# permamote.net
KiCad netlist of a schematic drawn in EAGLE
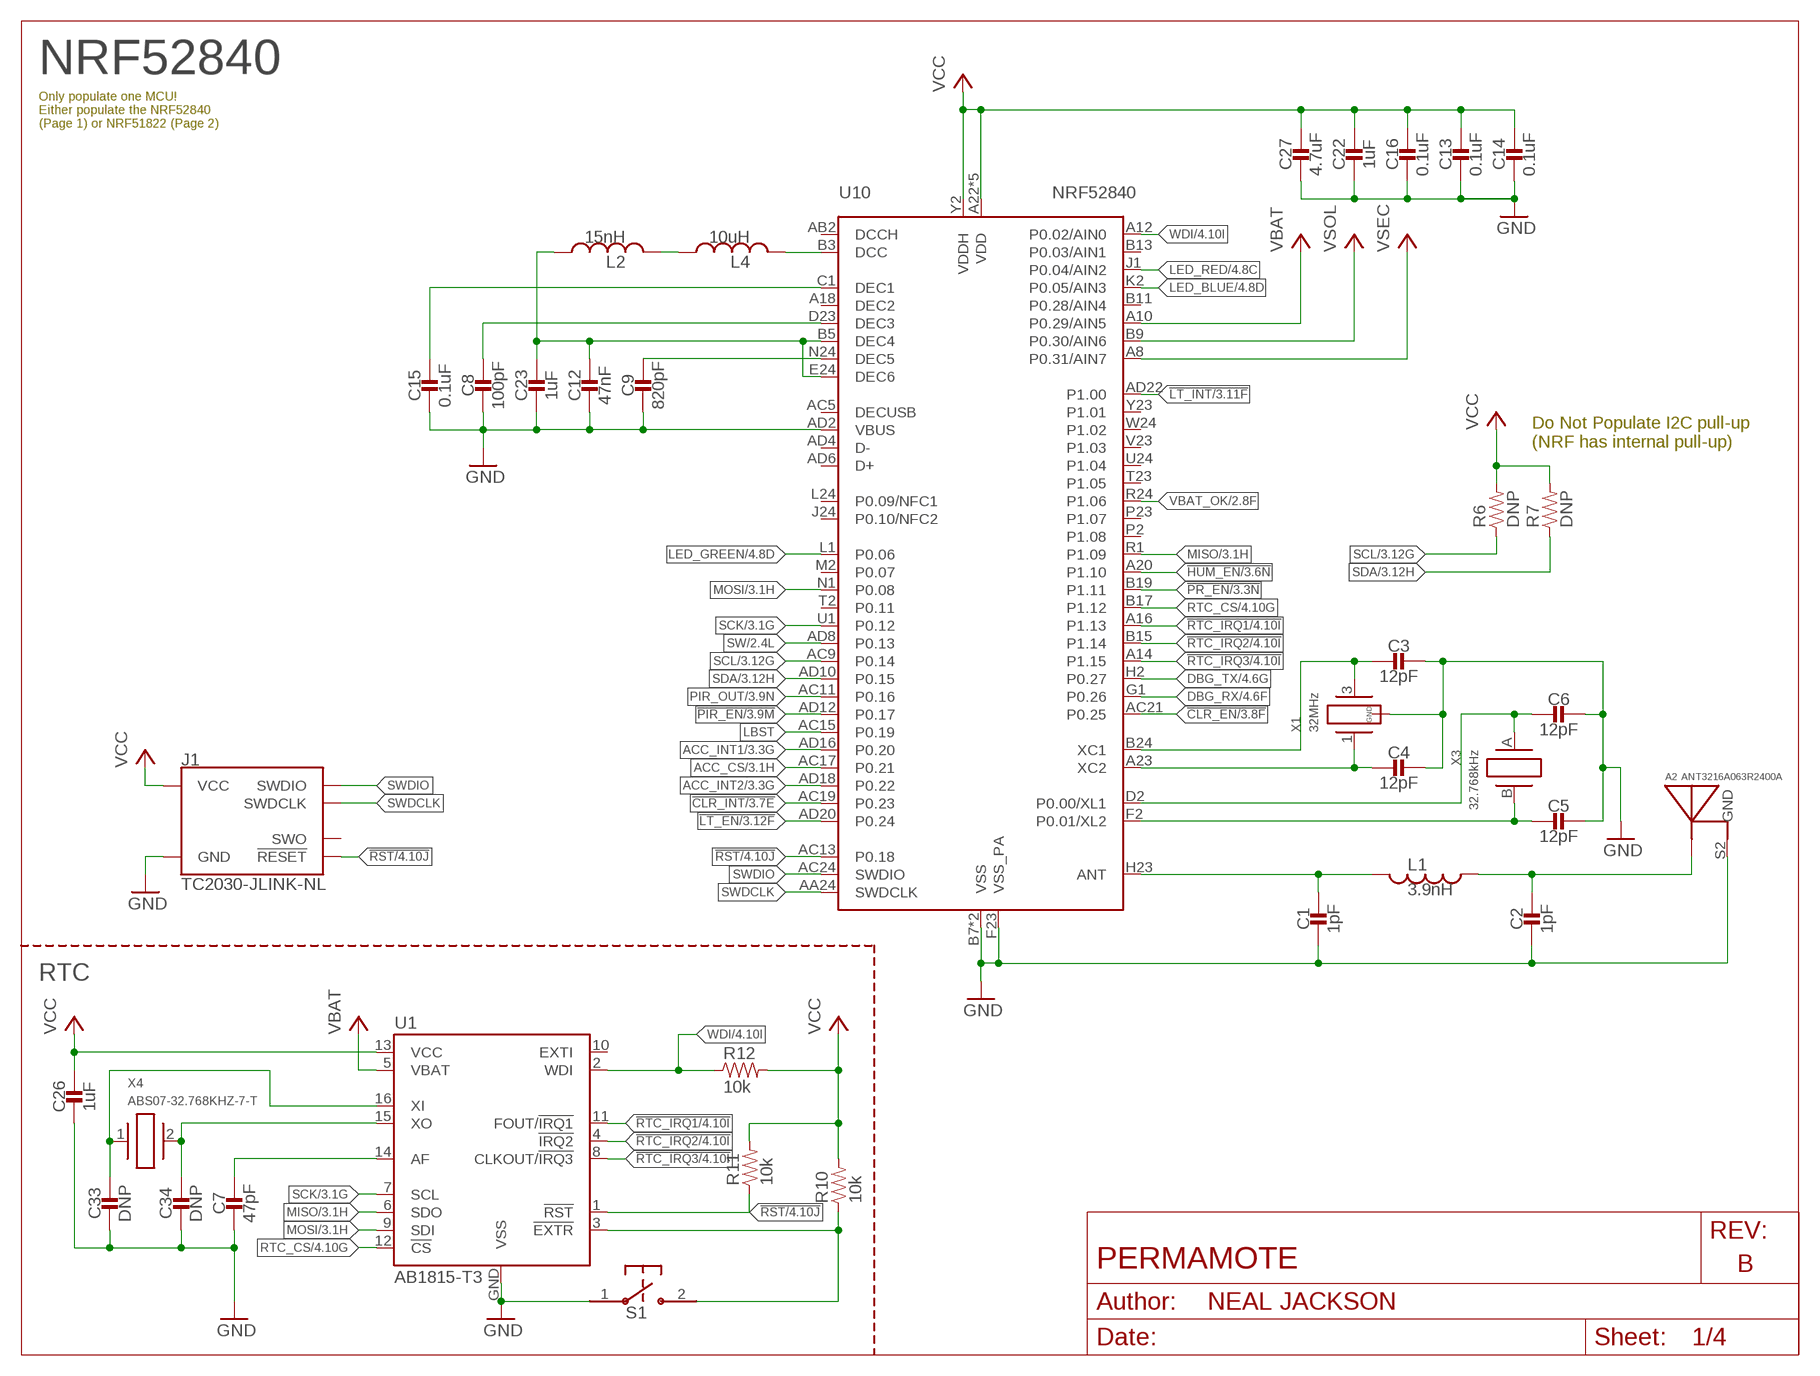
[diagram p0: schematic, sheet 1]
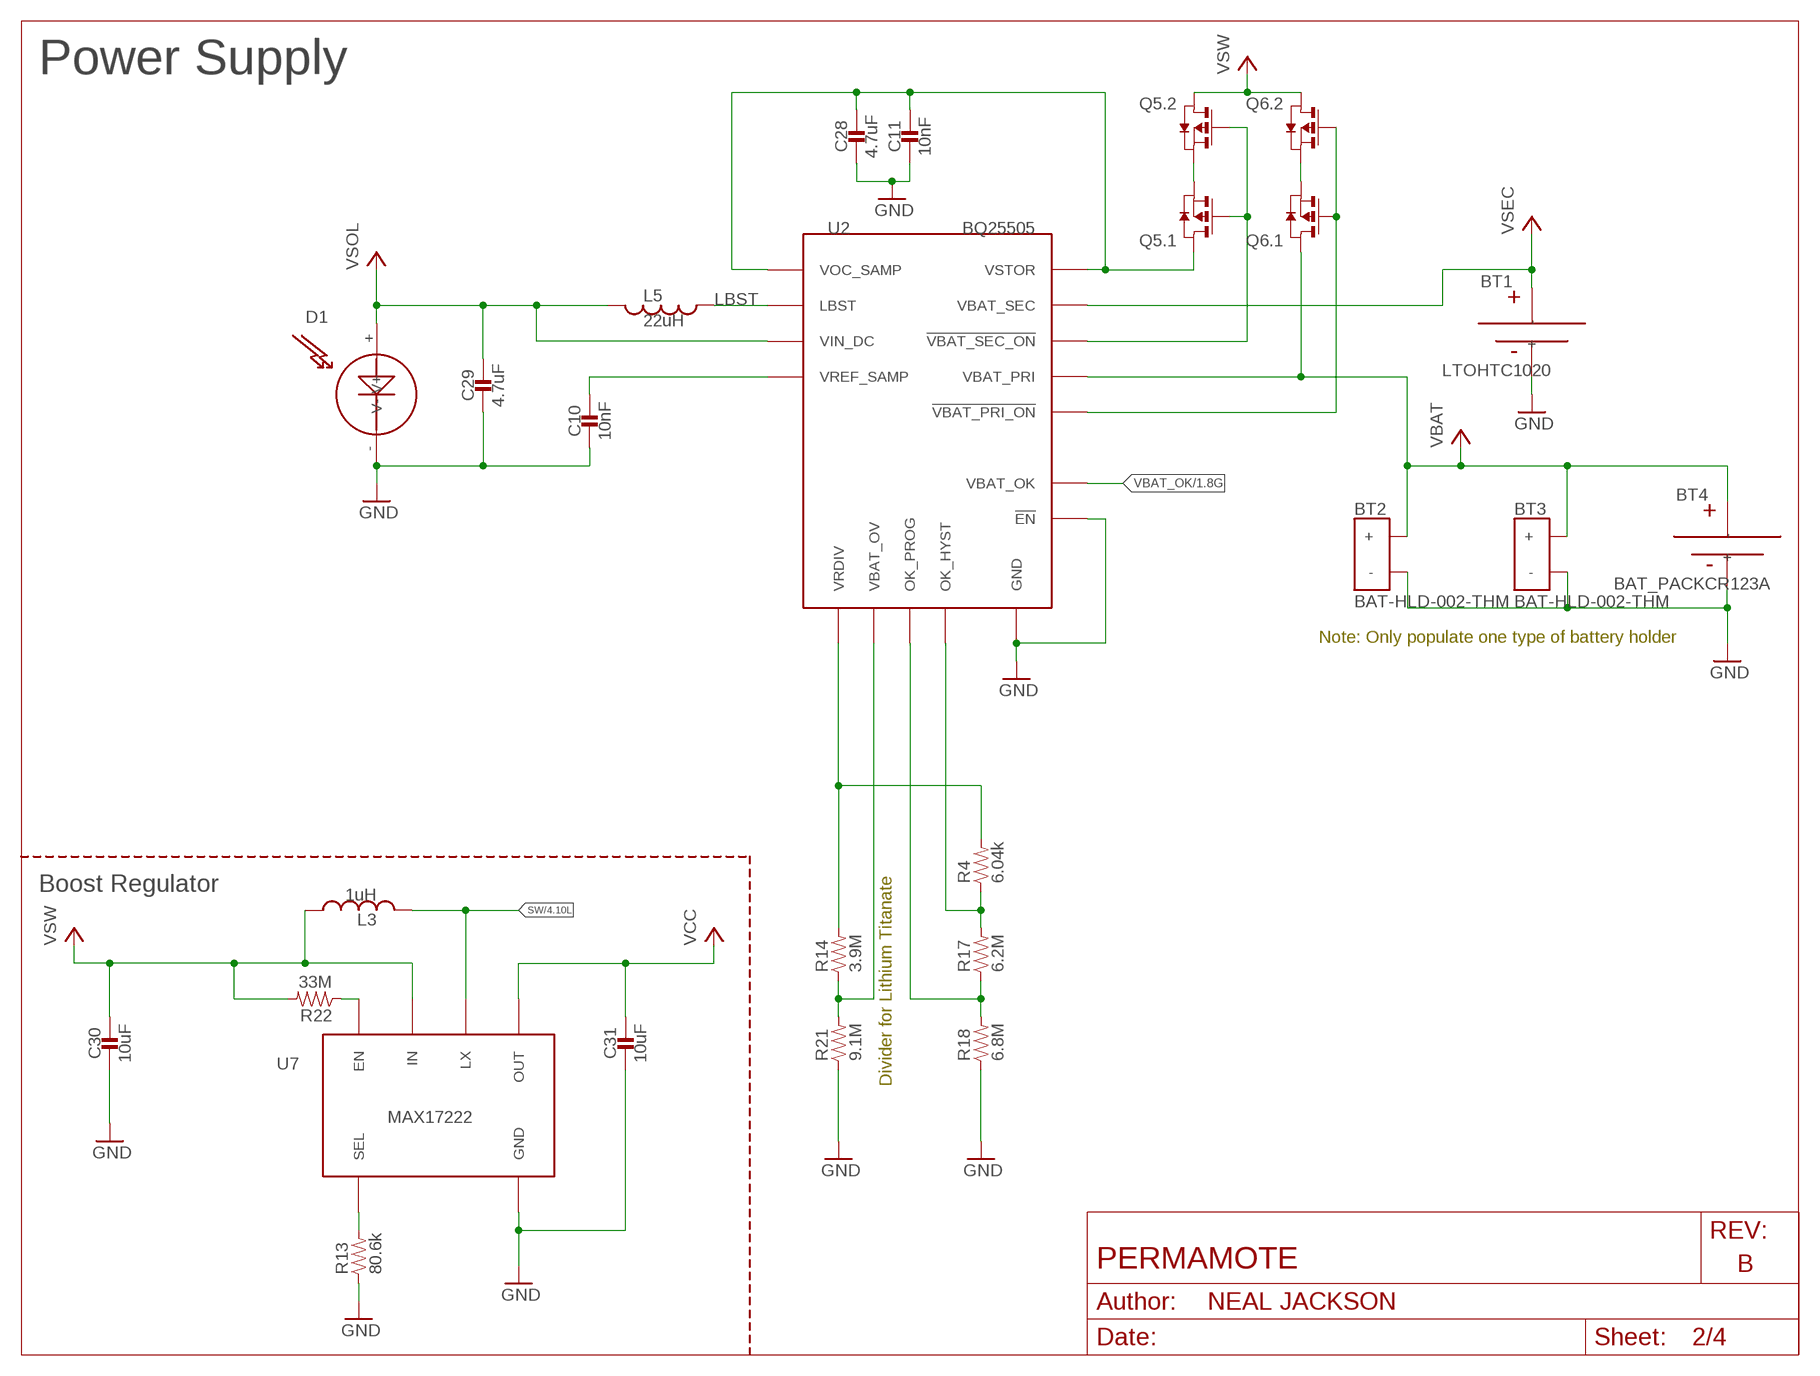
[diagram p1: schematic, sheet 2]
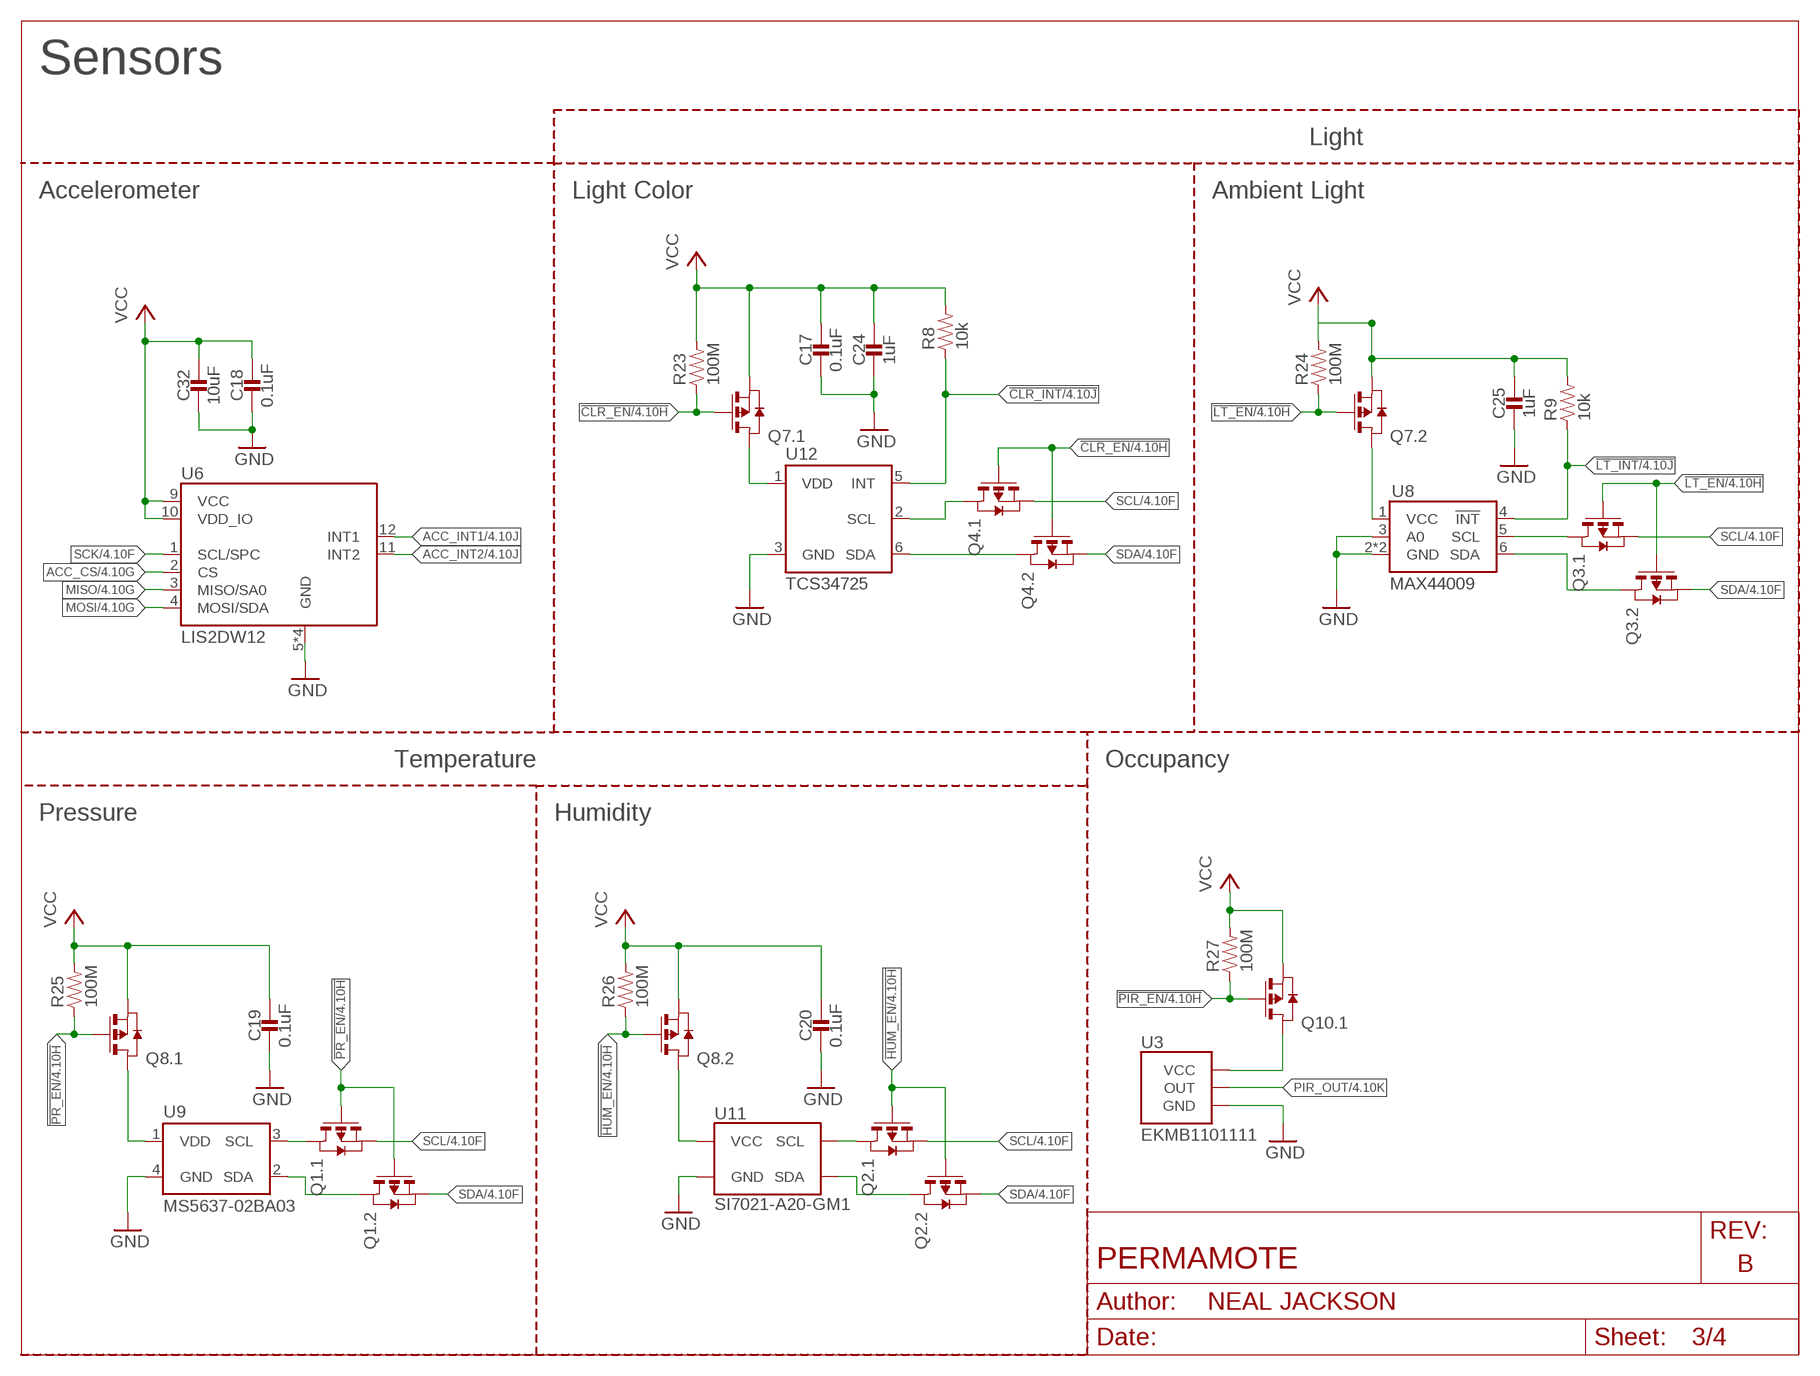
[diagram p2: schematic, sheet 3]
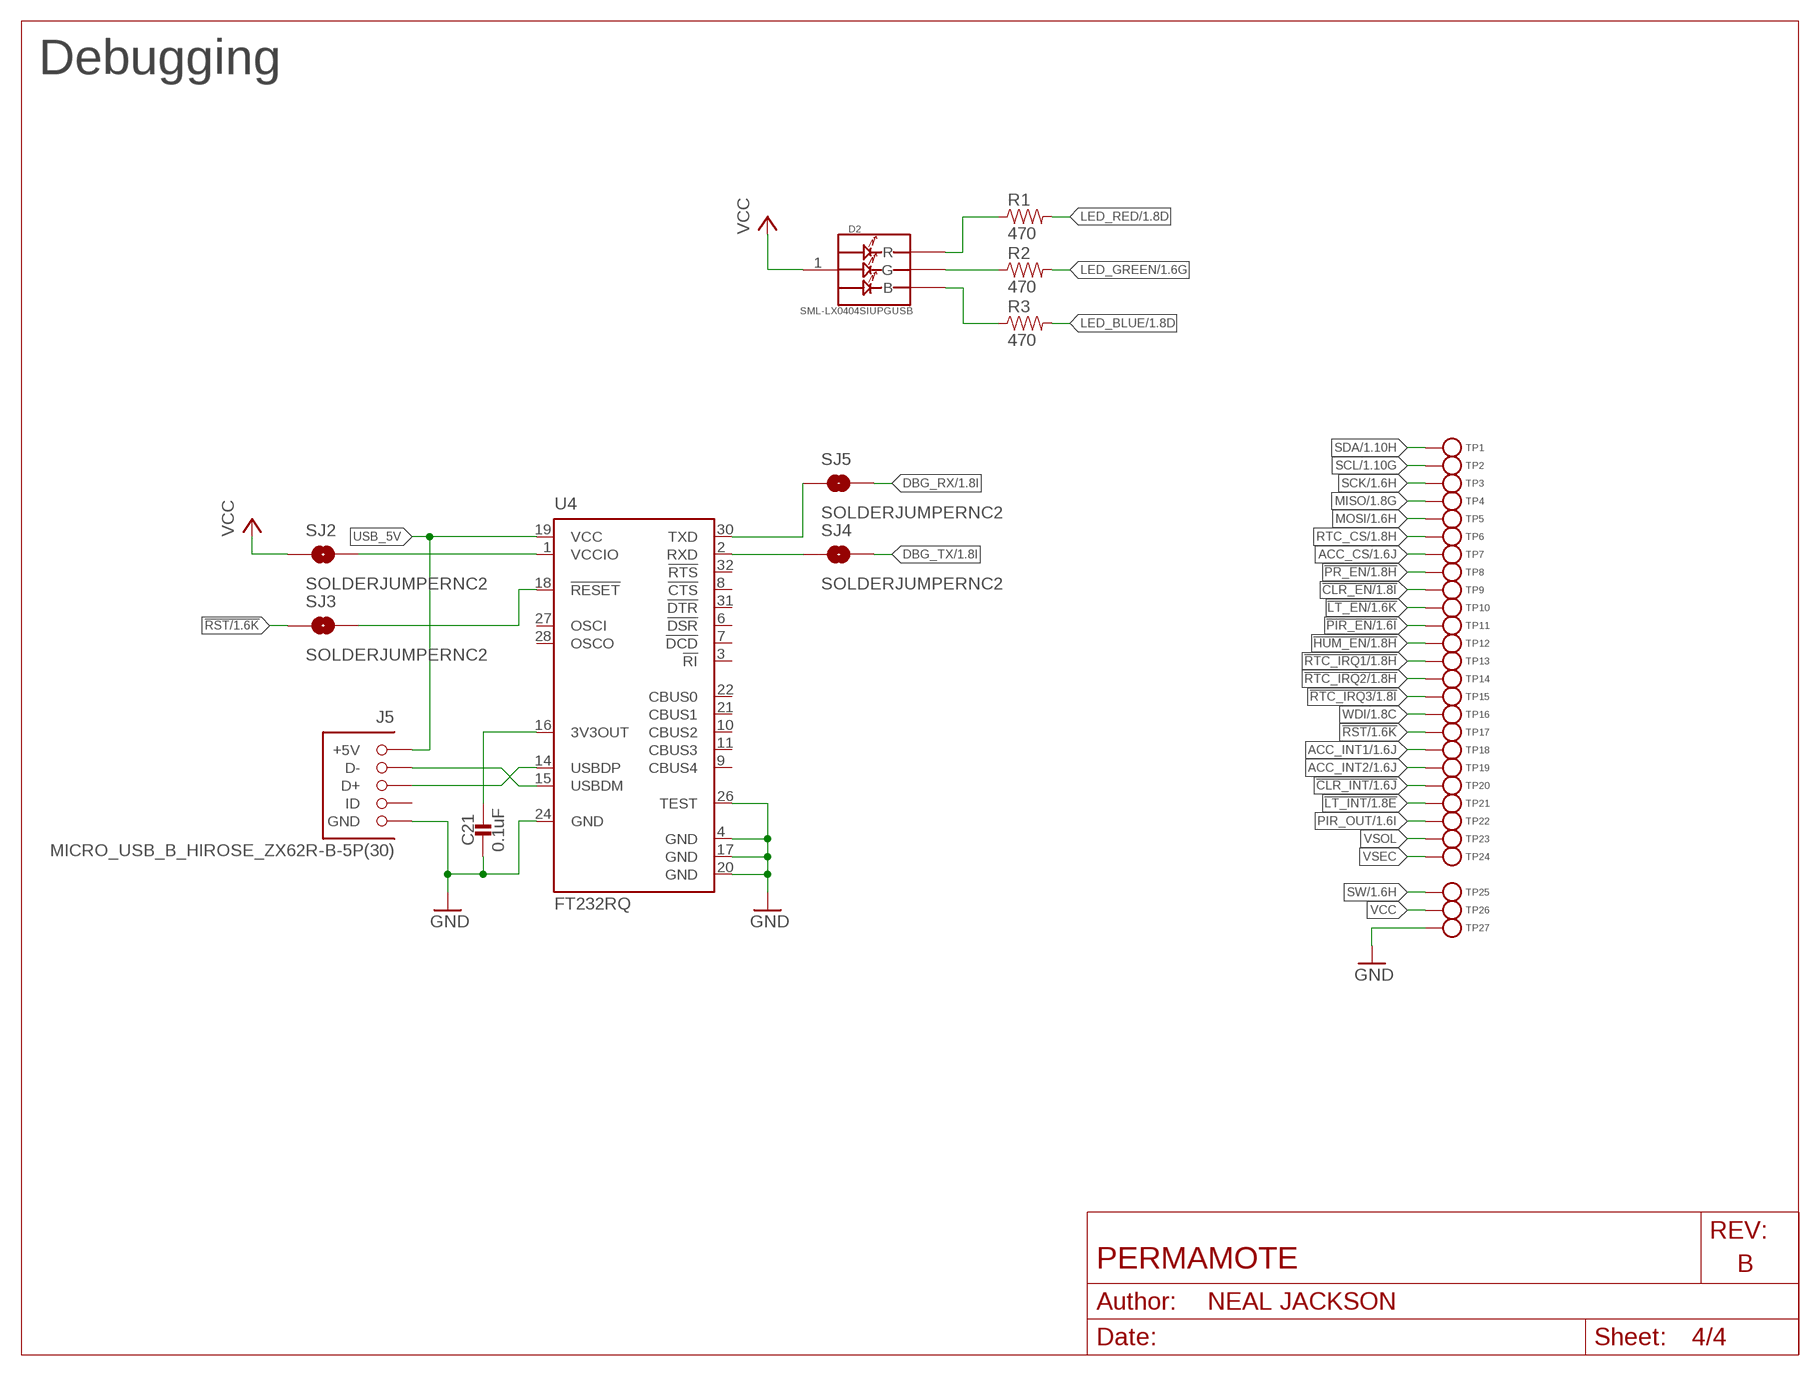
[diagram p3: schematic, sheet 4]

(export (version "E")
  (design (tool "Eeschema 10.0.6"))
  (components
    (comp (ref "BT1")
      (value "LTOHTC1020")
      (footprint "eagle-import:1020")
      (libsource (lib "eagle-import") (part "LTOHTC1020"))
    )
    (comp (ref "BT2")
      (value "BAT-HLD-002-THM")
      (footprint "eagle-import:BAT-HLD-002-THM")
      (fields
        (field (name "DIGIKEY") "BAT-HLD-001-THM-ND")
        (field (name "MOUSER") "712-BAT-HLD-001-THM")
        (field (name "MPN") "BAT-HLD-001-THM")
      )
      (libsource (lib "eagle-import") (part "BAT-HLD-002-THM"))
    )
    (comp (ref "BT3")
      (value "BAT-HLD-002-THM")
      (footprint "eagle-import:BAT-HLD-002-THM")
      (fields
        (field (name "DIGIKEY") "BAT-HLD-001-THM-ND")
        (field (name "MOUSER") "712-BAT-HLD-001-THM")
        (field (name "MPN") "BAT-HLD-001-THM")
      )
      (libsource (lib "eagle-import") (part "BAT-HLD-002-THM"))
    )
    (comp (ref "BT4")
      (value "BAT_PACKCR123A")
      (footprint "eagle-import:BH123A")
      (fields (field (name "MANUFACTURER") "MPD") (field (name "MPN") "BH123A"))
      (libsource (lib "eagle-import") (part "BAT_PACKCR123A"))
    )
    (comp (ref "C10")
      (value "10nF")
      (footprint "eagle-import:0402_CAP")
      (fields (field (name "MPN") "GRM155R71H103KA88D "))
      (libsource (lib "eagle-import") (part "CAPACITOR0402_CAP"))
    )
    (comp (ref "C11")
      (value "10nF")
      (footprint "eagle-import:0402_CAP")
      (fields (field (name "MPN") "GRM155R71H103KA88D "))
      (libsource (lib "eagle-import") (part "CAPACITOR0402_CAP"))
    )
    (comp (ref "C28")
      (value "4.7uF")
      (footprint "eagle-import:0402_CAP")
      (fields (field (name "MPN") "C1005X5R0J475K050BC "))
      (libsource (lib "eagle-import") (part "CAPACITOR0402_CAP"))
    )
    (comp (ref "C29")
      (value "4.7uF")
      (footprint "eagle-import:0402_CAP")
      (fields (field (name "MPN") "C1005X5R0J475K050BC "))
      (libsource (lib "eagle-import") (part "CAPACITOR0402_CAP"))
    )
    (comp (ref "C30")
      (value "10uF")
      (footprint "eagle-import:0603_CAP")
      (fields (field (name "MPN") "GRM188R60J106ME47D "))
      (libsource (lib "eagle-import") (part "CAPACITOR0603_CAP"))
    )
    (comp (ref "C31")
      (value "10uF")
      (footprint "eagle-import:0603_CAP")
      (fields (field (name "MPN") "GRM188R60J106ME47D "))
      (libsource (lib "eagle-import") (part "CAPACITOR0603_CAP"))
    )
    (comp (ref "D1")
      (value "SOLARCELLHOLES")
      (footprint "eagle-import:SOLAR_HOLES")
      (fields (field (name "MPN") "AM-1454CA"))
      (libsource (lib "eagle-import") (part "SOLARCELLHOLES"))
    )
    (comp (ref "L3")
      (value "1uH")
      (footprint "eagle-import:IHL-1212BZ-11")
      (fields
        (field (name "MANUFACTURER") "Vishay Dale")
        (field (name "MPN") "IHLP1212BZER2R2M11")
        (field (name "DIGIKEY") "541-1319-1-ND")
        (field (name "MPN_1") "IHLP1212BZER1R0M11")
      )
      (libsource (lib "eagle-import") (part "INDUCTORIHL"))
    )
    (comp (ref "L5")
      (value "22uH")
      (footprint "eagle-import:74437324220")
      (fields (field (name "DIGIKEY") "732-3340-1-ND") (field (name "MPN") "74437324220 "))
      (libsource (lib "eagle-import") (part "INDUCTOR74437324220"))
    )
    (comp (ref "Q5")
      (value "PMDXB950UPEL")
      (footprint "eagle-import:XDFN-6")
      (fields (field (name "MANUFACTURER") "NEXPERIA") (field (name "MPN") "PMDXB950UPELZ"))
      (libsource (lib "eagle-import") (part "PMDXB950UPEL"))
    )
    (comp (ref "Q6")
      (value "PMDXB950UPEL")
      (footprint "eagle-import:XDFN-6")
      (fields (field (name "MANUFACTURER") "NEXPERIA") (field (name "MPN") "PMDXB950UPELZ"))
      (libsource (lib "eagle-import") (part "PMDXB950UPEL"))
    )
    (comp (ref "R4")
      (value "6.04k")
      (footprint "eagle-import:0402_RES")
      (fields (field (name "MPN") "RC0402FR-076K04L"))
      (libsource (lib "eagle-import") (part "RESISTOR0402_RES"))
    )
    (comp (ref "R13")
      (value "80.6k")
      (footprint "eagle-import:0603-RES")
      (fields (field (name "MPN") "RC0603FR-0780K6L "))
      (libsource (lib "eagle-import") (part "RESISTOR0603_RES"))
    )
    (comp (ref "R14")
      (value "3.9M")
      (footprint "eagle-import:0402_RES")
      (fields (field (name "MPN") "RC0402JR-073M9L"))
      (libsource (lib "eagle-import") (part "RESISTOR0402_RES"))
    )
    (comp (ref "R17")
      (value "6.2M")
      (footprint "eagle-import:0402_RES")
      (fields (field (name "MPN") "RC0402JR-076M2L"))
      (libsource (lib "eagle-import") (part "RESISTOR0402_RES"))
    )
    (comp (ref "R18")
      (value "6.8M")
      (footprint "eagle-import:0402_RES")
      (fields (field (name "MPN") "RC0402JR-076M8L"))
      (libsource (lib "eagle-import") (part "RESISTOR0402_RES"))
    )
    (comp (ref "R21")
      (value "9.1M")
      (footprint "eagle-import:0402_RES")
      (fields (field (name "MPN") "RC0402JR-079M1L"))
      (libsource (lib "eagle-import") (part "RESISTOR0402_RES"))
    )
    (comp (ref "R22")
      (value "33M")
      (footprint "eagle-import:0603-RES")
      (fields (field (name "MPN") "HMC0603JT33M0 "))
      (libsource (lib "eagle-import") (part "RESISTOR0603_RES"))
    )
    (comp (ref "U2")
      (value "BQ25505")
      (footprint "eagle-import:S-PVQFN-N20-RGR")
      (fields (field (name "MANUFACTURER") "TI") (field (name "MPN") "BQ25505RGRR"))
      (libsource (lib "eagle-import") (part "BQ25505"))
    )
    (comp (ref "U7")
      (value "MAX17222")
      (footprint "eagle-import:UDFN-6-MAXIM")
      (fields (field (name "MANUFACTURER") "MAXIM INTEGRATED") (field (name "MPN") "MAX17222ELT+T"))
      (libsource (lib "eagle-import") (part "MAX17222"))
    )
    (comp (ref "A2")
      (value "ANT3216A063R2400A")
      (footprint "eagle-import:ANT3216A063R2400A")
      (fields (field (name "MANUFACTURER") "YAGEO"))
      (libsource (lib "eagle-import") (part "ANT3216A063R2400A"))
    )
    (comp (ref "C1")
      (value "1pF")
      (footprint "eagle-import:0402_CAP")
      (fields (field (name "MPN") "CL05C010CB5NNNC"))
      (libsource (lib "eagle-import") (part "CAPACITOR0402_CAP"))
    )
    (comp (ref "C2")
      (value "1pF")
      (footprint "eagle-import:0402_CAP")
      (fields (field (name "MPN") "CL05C010CB5NNNC"))
      (libsource (lib "eagle-import") (part "CAPACITOR0402_CAP"))
    )
    (comp (ref "C3")
      (value "12pF")
      (footprint "eagle-import:0402_CAP")
      (fields (field (name "MPN") "GRM1555C1H120GA01D "))
      (libsource (lib "eagle-import") (part "CAPACITOR0402_CAP"))
    )
    (comp (ref "C4")
      (value "12pF")
      (footprint "eagle-import:0402_CAP")
      (fields (field (name "MPN") "GRM1555C1H120GA01D "))
      (libsource (lib "eagle-import") (part "CAPACITOR0402_CAP"))
    )
    (comp (ref "C5")
      (value "12pF")
      (footprint "eagle-import:0402_CAP")
      (fields (field (name "MPN") "GRM1555C1H120GA01D "))
      (libsource (lib "eagle-import") (part "CAPACITOR0402_CAP"))
    )
    (comp (ref "C6")
      (value "12pF")
      (footprint "eagle-import:0402_CAP")
      (fields (field (name "MPN") "GRM1555C1H120GA01D "))
      (libsource (lib "eagle-import") (part "CAPACITOR0402_CAP"))
    )
    (comp (ref "C7")
      (value "47pF")
      (footprint "eagle-import:0402_CAP")
      (fields (field (name "MPN") "GRM1555C1H470JA01D "))
      (libsource (lib "eagle-import") (part "CAPACITOR0402_CAP"))
    )
    (comp (ref "C8")
      (value "100pF")
      (footprint "eagle-import:0402_CAP")
      (fields (field (name "MPN") "GRM1555C1H101JA01D "))
      (libsource (lib "eagle-import") (part "CAPACITOR0402_CAP"))
    )
    (comp (ref "C9")
      (value "820pF")
      (footprint "eagle-import:0402_CAP")
      (fields (field (name "MPN") "CL05B821KO5NNNC"))
      (libsource (lib "eagle-import") (part "CAPACITOR0402_CAP"))
    )
    (comp (ref "C12")
      (value "47nF")
      (footprint "eagle-import:0402_CAP")
      (fields (field (name "MPN") "C1005X7R1C473K050BC "))
      (libsource (lib "eagle-import") (part "CAPACITOR0402_CAP"))
    )
    (comp (ref "C13")
      (value "0.1uF")
      (footprint "eagle-import:0402_CAP")
      (fields (field (name "MPN") "GRM155R71C104KA88J "))
      (libsource (lib "eagle-import") (part "CAPACITOR0402_CAP"))
    )
    (comp (ref "C14")
      (value "0.1uF")
      (footprint "eagle-import:0402_CAP")
      (fields (field (name "MPN") "GRM155R71C104KA88J "))
      (libsource (lib "eagle-import") (part "CAPACITOR0402_CAP"))
    )
    (comp (ref "C15")
      (value "0.1uF")
      (footprint "eagle-import:0402_CAP")
      (fields (field (name "MPN") "GRM155R71C104KA88J "))
      (libsource (lib "eagle-import") (part "CAPACITOR0402_CAP"))
    )
    (comp (ref "C16")
      (value "0.1uF")
      (footprint "eagle-import:0402_CAP")
      (fields (field (name "MPN") "GRM155R71C104KA88J "))
      (libsource (lib "eagle-import") (part "CAPACITOR0402_CAP"))
    )
    (comp (ref "C22")
      (value "1uF")
      (footprint "eagle-import:0402_CAP")
      (fields (field (name "MPN") "GRM155R70G105KA12D "))
      (libsource (lib "eagle-import") (part "CAPACITOR0402_CAP"))
    )
    (comp (ref "C23")
      (value "1uF")
      (footprint "eagle-import:0402_CAP")
      (fields (field (name "MPN") "GRM155R70G105KA12D "))
      (libsource (lib "eagle-import") (part "CAPACITOR0402_CAP"))
    )
    (comp (ref "C26")
      (value "1uF")
      (footprint "eagle-import:0402_CAP")
      (fields (field (name "MPN") "GRM155R70G105KA12D "))
      (libsource (lib "eagle-import") (part "CAPACITOR0402_CAP"))
    )
    (comp (ref "C27")
      (value "4.7uF")
      (footprint "eagle-import:0402_CAP")
      (fields (field (name "MPN") "C1005X5R0J475K050BC "))
      (libsource (lib "eagle-import") (part "CAPACITOR0402_CAP"))
    )
    (comp (ref "C33")
      (value "DNP")
      (footprint "eagle-import:0402_CAP")
      (libsource (lib "eagle-import") (part "CAPACITOR0402_CAP"))
    )
    (comp (ref "C34")
      (value "DNP")
      (footprint "eagle-import:0402_CAP")
      (libsource (lib "eagle-import") (part "CAPACITOR0402_CAP"))
    )
    (comp (ref "J1")
      (value "TC2030-JLINK-NL")
      (footprint "eagle-import:TC2030-IDC-NL")
      (libsource (lib "eagle-import") (part "TC2030-JLINK-NL"))
    )
    (comp (ref "L1")
      (value "3.9nH")
      (footprint "eagle-import:0402_CAP")
      (fields (field (name "MPN") "LQP15MN3N9B02D"))
      (libsource (lib "eagle-import") (part "INDUCTOR0402"))
    )
    (comp (ref "L2")
      (value "15nH")
      (footprint "eagle-import:0402_CAP")
      (fields (field (name "MPN") "HK100515NJ-T "))
      (libsource (lib "eagle-import") (part "INDUCTOR0402"))
    )
    (comp (ref "L4")
      (value "10uH")
      (footprint "eagle-import:0603_CAP")
      (fields (field (name "MPN") "LQM18FN100M00D "))
      (libsource (lib "eagle-import") (part "INDUCTOR0603"))
    )
    (comp (ref "R6")
      (value "DNP")
      (footprint "eagle-import:0402_RES")
      (fields (field (name "MPN") "RC0402JR-0710KL"))
      (libsource (lib "eagle-import") (part "RESISTOR0402_RES"))
    )
    (comp (ref "R7")
      (value "DNP")
      (footprint "eagle-import:0402_RES")
      (fields (field (name "MPN") "RC0402JR-0710KL"))
      (libsource (lib "eagle-import") (part "RESISTOR0402_RES"))
    )
    (comp (ref "R10")
      (value "10k")
      (footprint "eagle-import:0402_RES")
      (fields (field (name "MPN") "RC0402JR-0710KL"))
      (libsource (lib "eagle-import") (part "RESISTOR0402_RES"))
    )
    (comp (ref "R11")
      (value "10k")
      (footprint "eagle-import:0402_RES")
      (fields (field (name "MPN") "RC0402JR-0710KL"))
      (libsource (lib "eagle-import") (part "RESISTOR0402_RES"))
    )
    (comp (ref "R12")
      (value "10k")
      (footprint "eagle-import:0402_RES")
      (fields (field (name "MPN") "RC0402JR-0710KL"))
      (libsource (lib "eagle-import") (part "RESISTOR0402_RES"))
    )
    (comp (ref "S1")
      (value "B3U-1000P")
      (footprint "eagle-import:B3U-1000P")
      (fields (field (name "MANUFACTURER") "Omron"))
      (libsource (lib "eagle-import") (part "B3U-1000P"))
    )
    (comp (ref "U1")
      (value "AB1815-T3")
      (footprint "eagle-import:QFN-16-3MM")
      (fields (field (name "MANUFACTURER") "Abracon"))
      (libsource (lib "eagle-import") (part "AB1815-T3"))
    )
    (comp (ref "U10")
      (value "NRF52840")
      (footprint "eagle-import:AQFN73")
      (fields (field (name "MANUFACTURER") "NORIDIC SEMICONDUCTOR"))
      (libsource (lib "eagle-import") (part "NRF52840"))
    )
    (comp (ref "X1")
      (value "32MHz")
      (footprint "eagle-import:TXC-7V")
      (fields (field (name "MANUFACTURER") "TXC CORPORATION") (field (name "MPN") "7M-32.000MAHV-T"))
      (libsource (lib "eagle-import") (part "7V-32.000MAHV-T"))
    )
    (comp (ref "X3")
      (value "32.768kHz")
      (footprint "eagle-import:ABS05")
      (fields (field (name "MANUFACTURER") "Abracon") (field (name "MPN") "ABS05-32.768KHZ-9-T"))
      (libsource (lib "eagle-import") (part "ABS05-32.768KHZ-9-T"))
    )
    (comp (ref "X4")
      (value "ABS07-32.768KHZ-7-T")
      (footprint "eagle-import:2-SMD")
      (fields (field (name "MANUFACTURER") "ABRACON") (field (name "MPN") "ABS07-32.768KHZ-7-T "))
      (libsource (lib "eagle-import") (part "ABS07-32.768KHZ-7-T"))
    )
    (comp (ref "C21")
      (value "0.1uF")
      (footprint "eagle-import:0402_CAP")
      (fields (field (name "MPN") "GRM155R71C104KA88J "))
      (libsource (lib "eagle-import") (part "CAPACITOR0402_CAP"))
    )
    (comp (ref "D2")
      (value "SML-LX0404SIUPGUSB")
      (footprint "eagle-import:1MM_SQ_4PAD")
      (fields (field (name "MANUFACTURER") "Lumex Opto"))
      (libsource (lib "eagle-import") (part "SML-LX0404SIUPGUSB"))
    )
    (comp (ref "J5")
      (value "MICRO_USB_B_HIROSE_ZX62R-B-5P(30)")
      (footprint "eagle-import:MICRO_USB_B_HIROSE_ZX62R-B-5P(30)")
      (fields (field (name "MPN") "ZX62R-B-5P(30)"))
      (libsource (lib "eagle-import") (part "MICRO_USB_B_HIROSE_ZX62R-B-5P(30)"))
    )
    (comp (ref "R1")
      (value "470")
      (footprint "eagle-import:0402_RES")
      (fields (field (name "MPN") "RC0402JR-07470RL "))
      (libsource (lib "eagle-import") (part "RESISTOR0402_RES"))
    )
    (comp (ref "R2")
      (value "470")
      (footprint "eagle-import:0402_RES")
      (fields (field (name "MPN") "RC0402JR-07470RL "))
      (libsource (lib "eagle-import") (part "RESISTOR0402_RES"))
    )
    (comp (ref "R3")
      (value "470")
      (footprint "eagle-import:0402_RES")
      (fields (field (name "MPN") "RC0402JR-07470RL "))
      (libsource (lib "eagle-import") (part "RESISTOR0402_RES"))
    )
    (comp (ref "SJ2")
      (value "SOLDERJUMPERNC2")
      (footprint "eagle-import:SJ_2S-NOTRACE")
      (libsource (lib "eagle-import") (part "SOLDERJUMPERNC2"))
    )
    (comp (ref "SJ3")
      (value "SOLDERJUMPERNC2")
      (footprint "eagle-import:SJ_2S-NOTRACE")
      (libsource (lib "eagle-import") (part "SOLDERJUMPERNC2"))
    )
    (comp (ref "SJ4")
      (value "SOLDERJUMPERNC2")
      (footprint "eagle-import:SJ_2S-NOTRACE")
      (libsource (lib "eagle-import") (part "SOLDERJUMPERNC2"))
    )
    (comp (ref "SJ5")
      (value "SOLDERJUMPERNC2")
      (footprint "eagle-import:SJ_2S-NOTRACE")
      (libsource (lib "eagle-import") (part "SOLDERJUMPERNC2"))
    )
    (comp (ref "TP1")
      (value "TEST-POINT")
      (footprint "eagle-import:PAD.03X.03")
      (libsource (lib "eagle-import") (part "TEST-POINT"))
    )
    (comp (ref "TP2")
      (value "TEST-POINT")
      (footprint "eagle-import:PAD.03X.03")
      (libsource (lib "eagle-import") (part "TEST-POINT"))
    )
    (comp (ref "TP3")
      (value "TEST-POINT")
      (footprint "eagle-import:PAD.03X.03")
      (libsource (lib "eagle-import") (part "TEST-POINT"))
    )
    (comp (ref "TP4")
      (value "TEST-POINT")
      (footprint "eagle-import:PAD.03X.03")
      (libsource (lib "eagle-import") (part "TEST-POINT"))
    )
    (comp (ref "TP5")
      (value "TEST-POINT")
      (footprint "eagle-import:PAD.03X.03")
      (libsource (lib "eagle-import") (part "TEST-POINT"))
    )
    (comp (ref "TP6")
      (value "TEST-POINT")
      (footprint "eagle-import:PAD.03X.03")
      (libsource (lib "eagle-import") (part "TEST-POINT"))
    )
    (comp (ref "TP7")
      (value "TEST-POINT")
      (footprint "eagle-import:PAD.03X.03")
      (libsource (lib "eagle-import") (part "TEST-POINT"))
    )
    (comp (ref "TP8")
      (value "TEST-POINT")
      (footprint "eagle-import:PAD.03X.03")
      (libsource (lib "eagle-import") (part "TEST-POINT"))
    )
    (comp (ref "TP9")
      (value "TEST-POINT")
      (footprint "eagle-import:PAD.03X.03")
      (libsource (lib "eagle-import") (part "TEST-POINT"))
    )
    (comp (ref "TP10")
      (value "TEST-POINT")
      (footprint "eagle-import:PAD.03X.03")
      (libsource (lib "eagle-import") (part "TEST-POINT"))
    )
    (comp (ref "TP11")
      (value "TEST-POINT")
      (footprint "eagle-import:PAD.03X.03")
      (libsource (lib "eagle-import") (part "TEST-POINT"))
    )
    (comp (ref "TP12")
      (value "TEST-POINT")
      (footprint "eagle-import:PAD.03X.03")
      (libsource (lib "eagle-import") (part "TEST-POINT"))
    )
    (comp (ref "TP13")
      (value "TEST-POINT")
      (footprint "eagle-import:PAD.03X.03")
      (libsource (lib "eagle-import") (part "TEST-POINT"))
    )
    (comp (ref "TP14")
      (value "TEST-POINT")
      (footprint "eagle-import:PAD.03X.03")
      (libsource (lib "eagle-import") (part "TEST-POINT"))
    )
    (comp (ref "TP15")
      (value "TEST-POINT")
      (footprint "eagle-import:PAD.03X.03")
      (libsource (lib "eagle-import") (part "TEST-POINT"))
    )
    (comp (ref "TP16")
      (value "TEST-POINT")
      (footprint "eagle-import:PAD.03X.03")
      (libsource (lib "eagle-import") (part "TEST-POINT"))
    )
    (comp (ref "TP17")
      (value "TEST-POINT")
      (footprint "eagle-import:PAD.03X.03")
      (libsource (lib "eagle-import") (part "TEST-POINT"))
    )
    (comp (ref "TP18")
      (value "TEST-POINT")
      (footprint "eagle-import:PAD.03X.03")
      (libsource (lib "eagle-import") (part "TEST-POINT"))
    )
    (comp (ref "TP19")
      (value "TEST-POINT")
      (footprint "eagle-import:PAD.03X.03")
      (libsource (lib "eagle-import") (part "TEST-POINT"))
    )
    (comp (ref "TP20")
      (value "TEST-POINT")
      (footprint "eagle-import:PAD.03X.03")
      (libsource (lib "eagle-import") (part "TEST-POINT"))
    )
    (comp (ref "TP21")
      (value "TEST-POINT")
      (footprint "eagle-import:PAD.03X.03")
      (libsource (lib "eagle-import") (part "TEST-POINT"))
    )
    (comp (ref "TP22")
      (value "TEST-POINT")
      (footprint "eagle-import:PAD.03X.03")
      (libsource (lib "eagle-import") (part "TEST-POINT"))
    )
    (comp (ref "TP23")
      (value "TEST-POINT")
      (footprint "eagle-import:PAD.03X.03")
      (libsource (lib "eagle-import") (part "TEST-POINT"))
    )
    (comp (ref "TP24")
      (value "TEST-POINT")
      (footprint "eagle-import:PAD.03X.03")
      (libsource (lib "eagle-import") (part "TEST-POINT"))
    )
    (comp (ref "TP25")
      (value "TEST-POINT")
      (footprint "eagle-import:PAD.03X.03")
      (libsource (lib "eagle-import") (part "TEST-POINT"))
    )
    (comp (ref "TP26")
      (value "TEST-POINT")
      (footprint "eagle-import:PAD.03X.03")
      (libsource (lib "eagle-import") (part "TEST-POINT"))
    )
    (comp (ref "TP27")
      (value "TEST-POINT")
      (footprint "eagle-import:PAD.03X.03")
      (libsource (lib "eagle-import") (part "TEST-POINT"))
    )
    (comp (ref "U4")
      (value "FT232RQ")
      (footprint "eagle-import:QFN32")
      (libsource (lib "eagle-import") (part "FT232RQ"))
    )
    (comp (ref "C17")
      (value "0.1uF")
      (footprint "eagle-import:0402_CAP")
      (fields (field (name "MPN") "GRM155R71C104KA88J "))
      (libsource (lib "eagle-import") (part "CAPACITOR0402_CAP"))
    )
    (comp (ref "C18")
      (value "0.1uF")
      (footprint "eagle-import:0402_CAP")
      (fields (field (name "MPN") "GRM155R71C104KA88J "))
      (libsource (lib "eagle-import") (part "CAPACITOR0402_CAP"))
    )
    (comp (ref "C19")
      (value "0.1uF")
      (footprint "eagle-import:0402_CAP")
      (fields (field (name "MPN") "GRM155R71C104KA88J "))
      (libsource (lib "eagle-import") (part "CAPACITOR0402_CAP"))
    )
    (comp (ref "C20")
      (value "0.1uF")
      (footprint "eagle-import:0402_CAP")
      (fields (field (name "MPN") "GRM155R71C104KA88J "))
      (libsource (lib "eagle-import") (part "CAPACITOR0402_CAP"))
    )
    (comp (ref "C24")
      (value "1uF")
      (footprint "eagle-import:0402_CAP")
      (fields (field (name "MPN") "GRM155R70G105KA12D "))
      (libsource (lib "eagle-import") (part "CAPACITOR0402_CAP"))
    )
    (comp (ref "C25")
      (value "1uF")
      (footprint "eagle-import:0402_CAP")
      (fields (field (name "MPN") "GRM155R70G105KA12D "))
      (libsource (lib "eagle-import") (part "CAPACITOR0402_CAP"))
    )
    (comp (ref "C32")
      (value "10uF")
      (footprint "eagle-import:0603_CAP")
      (fields (field (name "MPN") "GRM188R60J106ME47D "))
      (libsource (lib "eagle-import") (part "CAPACITOR0603_CAP"))
    )
    (comp (ref "Q1")
      (value "PMDXB950UPEL")
      (footprint "eagle-import:XDFN-6")
      (fields (field (name "MANUFACTURER") "NEXPERIA") (field (name "MPN") "PMDXB950UPELZ"))
      (libsource (lib "eagle-import") (part "PMDXB950UPEL"))
    )
    (comp (ref "Q2")
      (value "PMDXB950UPEL")
      (footprint "eagle-import:XDFN-6")
      (fields (field (name "MANUFACTURER") "NEXPERIA") (field (name "MPN") "PMDXB950UPELZ"))
      (libsource (lib "eagle-import") (part "PMDXB950UPEL"))
    )
    (comp (ref "Q3")
      (value "PMDXB950UPEL")
      (footprint "eagle-import:XDFN-6")
      (fields (field (name "MANUFACTURER") "NEXPERIA") (field (name "MPN") "PMDXB950UPELZ"))
      (libsource (lib "eagle-import") (part "PMDXB950UPEL"))
    )
    (comp (ref "Q4")
      (value "PMDXB950UPEL")
      (footprint "eagle-import:XDFN-6")
      (fields (field (name "MANUFACTURER") "NEXPERIA") (field (name "MPN") "PMDXB950UPELZ"))
      (libsource (lib "eagle-import") (part "PMDXB950UPEL"))
    )
    (comp (ref "Q7")
      (value "PMDXB950UPEL")
      (footprint "eagle-import:XDFN-6")
      (fields (field (name "MANUFACTURER") "NEXPERIA") (field (name "MPN") "PMDXB950UPELZ"))
      (libsource (lib "eagle-import") (part "PMDXB950UPEL"))
    )
    (comp (ref "Q8")
      (value "PMDXB950UPEL")
      (footprint "eagle-import:XDFN-6")
      (fields (field (name "MANUFACTURER") "NEXPERIA") (field (name "MPN") "PMDXB950UPELZ"))
      (libsource (lib "eagle-import") (part "PMDXB950UPEL"))
    )
    (comp (ref "Q10")
      (value "PMDXB950UPEL")
      (footprint "eagle-import:XDFN-6")
      (fields (field (name "MANUFACTURER") "NEXPERIA") (field (name "MPN") "PMDXB950UPELZ"))
      (libsource (lib "eagle-import") (part "PMDXB950UPEL"))
    )
    (comp (ref "R8")
      (value "10k")
      (footprint "eagle-import:0402_RES")
      (fields (field (name "MPN") "RC0402JR-0710KL"))
      (libsource (lib "eagle-import") (part "RESISTOR0402_RES"))
    )
    (comp (ref "R9")
      (value "10k")
      (footprint "eagle-import:0402_RES")
      (fields (field (name "MPN") "RC0402JR-0710KL"))
      (libsource (lib "eagle-import") (part "RESISTOR0402_RES"))
    )
    (comp (ref "R23")
      (value "100M")
      (footprint "eagle-import:0402_RES")
      (fields (field (name "MPN") "HMC0402JT100M "))
      (libsource (lib "eagle-import") (part "RESISTOR0402_RES"))
    )
    (comp (ref "R24")
      (value "100M")
      (footprint "eagle-import:0402_RES")
      (fields (field (name "MPN") "HMC0402JT100M "))
      (libsource (lib "eagle-import") (part "RESISTOR0402_RES"))
    )
    (comp (ref "R25")
      (value "100M")
      (footprint "eagle-import:0402_RES")
      (fields (field (name "MPN") "HMC0402JT100M "))
      (libsource (lib "eagle-import") (part "RESISTOR0402_RES"))
    )
    (comp (ref "R26")
      (value "100M")
      (footprint "eagle-import:0402_RES")
      (fields (field (name "MPN") "HMC0402JT100M "))
      (libsource (lib "eagle-import") (part "RESISTOR0402_RES"))
    )
    (comp (ref "R27")
      (value "100M")
      (footprint "eagle-import:0402_RES")
      (fields (field (name "MPN") "HMC0402JT100M "))
      (libsource (lib "eagle-import") (part "RESISTOR0402_RES"))
    )
    (comp (ref "U3")
      (value "EKMB1101111")
      (footprint "eagle-import:AMN2")
      (fields (field (name "MANUFACTURER") "PANASONIC"))
      (libsource (lib "eagle-import") (part "EKMB1101111"))
    )
    (comp (ref "U6")
      (value "LIS2DW12")
      (footprint "eagle-import:LGA-12")
      (fields (field (name "MANUFACTURER") "STMicroelectronics") (field (name "MPN") "LIS2DW12TR"))
      (libsource (lib "eagle-import") (part "LIS2DW12"))
    )
    (comp (ref "U8")
      (value "MAX44009")
      (footprint "eagle-import:UDFN-6-EXPOSED")
      (fields (field (name "MANUFACTURER") "MAXIM") (field (name "MPN") "MAX44009EDT+T"))
      (libsource (lib "eagle-import") (part "MAX44009"))
    )
    (comp (ref "U9")
      (value "MS5637-02BA03")
      (footprint "eagle-import:4-SMD")
      (fields (field (name "MANUFACTURER") "TE CONNECTIVITY") (field (name "MPN") "MS563702BA03-50"))
      (libsource (lib "eagle-import") (part "MS5637-02BA03"))
    )
    (comp (ref "U11")
      (value "SI7021-A20-GM1")
      (footprint "eagle-import:DFN-6_3MM")
      (fields (field (name "MPN") "SI7021-A20-GM1 "))
      (libsource (lib "eagle-import") (part "SI7021-A20-GM1"))
    )
    (comp (ref "U12")
      (value "TCS34725")
      (footprint "eagle-import:FN-6")
      (fields (field (name "MPN") "TCS34725FN"))
      (libsource (lib "eagle-import") (part "TCS34725"))
    )
  )
  (nets
    (net (code "1") (name "ACC_CS") (class "Default")
      (node (ref "TP7") (pin "P$1") (pinfunction "TESTPOINT_P$1") (pintype "bidirectional"))
      (node (ref "U10") (pin "AC17") (pinfunction "P0.21_AC17") (pintype "bidirectional"))
      (node (ref "U6") (pin "2") (pinfunction "CS_2") (pintype "bidirectional"))
    )
    (net (code "2") (name "ACC_INT1") (class "Default")
      (node (ref "TP18") (pin "P$1") (pinfunction "TESTPOINT_P$1") (pintype "bidirectional"))
      (node (ref "U10") (pin "AD16") (pinfunction "P0.20_AD16") (pintype "bidirectional"))
      (node (ref "U6") (pin "12") (pinfunction "INT1_12") (pintype "bidirectional"))
    )
    (net (code "3") (name "ACC_INT2") (class "Default")
      (node (ref "TP19") (pin "P$1") (pinfunction "TESTPOINT_P$1") (pintype "bidirectional"))
      (node (ref "U10") (pin "AD18") (pinfunction "P0.22_AD18") (pintype "bidirectional"))
      (node (ref "U6") (pin "11") (pinfunction "INT2_11") (pintype "bidirectional"))
    )
    (net (code "4") (name "DBG_RX") (class "Default")
      (node (ref "SJ5") (pin "2") (pinfunction "2_2") (pintype "passive"))
      (node (ref "U10") (pin "G1") (pinfunction "P0.26_G1") (pintype "bidirectional"))
    )
    (net (code "5") (name "DBG_TX") (class "Default")
      (node (ref "SJ4") (pin "2") (pinfunction "2_2") (pintype "passive"))
      (node (ref "U10") (pin "H2") (pinfunction "P0.27_H2") (pintype "bidirectional"))
    )
    (net (code "6") (name "GND") (class "Default")
      (node (ref "A2") (pin "S2") (pinfunction "GND_S2") (pintype "bidirectional"))
      (node (ref "BT1") (pin "-") (pinfunction "-_-") (pintype "bidirectional"))
      (node (ref "BT2") (pin "GND") (pinfunction "-_GND") (pintype "bidirectional"))
      (node (ref "BT3") (pin "GND") (pinfunction "-_GND") (pintype "bidirectional"))
      (node (ref "BT4") (pin "-") (pinfunction "-_-") (pintype "bidirectional"))
      (node (ref "C1") (pin "2") (pinfunction "2_2") (pintype "bidirectional"))
      (node (ref "C10") (pin "2") (pinfunction "2_2") (pintype "bidirectional"))
      (node (ref "C11") (pin "2") (pinfunction "2_2") (pintype "bidirectional"))
      (node (ref "C12") (pin "2") (pinfunction "2_2") (pintype "bidirectional"))
      (node (ref "C13") (pin "2") (pinfunction "2_2") (pintype "bidirectional"))
      (node (ref "C14") (pin "2") (pinfunction "2_2") (pintype "bidirectional"))
      (node (ref "C15") (pin "2") (pinfunction "2_2") (pintype "bidirectional"))
      (node (ref "C16") (pin "2") (pinfunction "2_2") (pintype "bidirectional"))
      (node (ref "C17") (pin "2") (pinfunction "2_2") (pintype "bidirectional"))
      (node (ref "C18") (pin "2") (pinfunction "2_2") (pintype "bidirectional"))
      (node (ref "C19") (pin "2") (pinfunction "2_2") (pintype "bidirectional"))
      (node (ref "C2") (pin "2") (pinfunction "2_2") (pintype "bidirectional"))
      (node (ref "C20") (pin "2") (pinfunction "2_2") (pintype "bidirectional"))
      (node (ref "C21") (pin "2") (pinfunction "2_2") (pintype "bidirectional"))
      (node (ref "C22") (pin "2") (pinfunction "2_2") (pintype "bidirectional"))
      (node (ref "C23") (pin "2") (pinfunction "2_2") (pintype "bidirectional"))
      (node (ref "C24") (pin "2") (pinfunction "2_2") (pintype "bidirectional"))
      (node (ref "C25") (pin "2") (pinfunction "2_2") (pintype "bidirectional"))
      (node (ref "C26") (pin "2") (pinfunction "2_2") (pintype "bidirectional"))
      (node (ref "C27") (pin "2") (pinfunction "2_2") (pintype "bidirectional"))
      (node (ref "C28") (pin "2") (pinfunction "2_2") (pintype "bidirectional"))
      (node (ref "C29") (pin "2") (pinfunction "2_2") (pintype "bidirectional"))
      (node (ref "C3") (pin "1") (pinfunction "1_1") (pintype "bidirectional"))
      (node (ref "C30") (pin "2") (pinfunction "2_2") (pintype "bidirectional"))
      (node (ref "C31") (pin "2") (pinfunction "2_2") (pintype "bidirectional"))
      (node (ref "C32") (pin "2") (pinfunction "2_2") (pintype "bidirectional"))
      (node (ref "C33") (pin "2") (pinfunction "2_2") (pintype "bidirectional"))
      (node (ref "C34") (pin "2") (pinfunction "2_2") (pintype "bidirectional"))
      (node (ref "C4") (pin "1") (pinfunction "1_1") (pintype "bidirectional"))
      (node (ref "C5") (pin "1") (pinfunction "1_1") (pintype "bidirectional"))
      (node (ref "C6") (pin "1") (pinfunction "1_1") (pintype "bidirectional"))
      (node (ref "C7") (pin "2") (pinfunction "2_2") (pintype "bidirectional"))
      (node (ref "C8") (pin "2") (pinfunction "2_2") (pintype "bidirectional"))
      (node (ref "C9") (pin "2") (pinfunction "2_2") (pintype "bidirectional"))
      (node (ref "D1") (pin "-") (pinfunction "V-_-") (pintype "bidirectional"))
      (node (ref "J1") (pin "5") (pinfunction "GND_5") (pintype "bidirectional"))
      (node (ref "J5") (pin "5") (pinfunction "GND_5") (pintype "bidirectional"))
      (node (ref "R13") (pin "1") (pinfunction "1_1") (pintype "passive"))
      (node (ref "R18") (pin "1") (pinfunction "1_1") (pintype "passive"))
      (node (ref "R21") (pin "1") (pinfunction "1_1") (pintype "passive"))
      (node (ref "S1") (pin "1") (pinfunction "P$1_1") (pintype "passive"))
      (node (ref "TP27") (pin "P$1") (pinfunction "TESTPOINT_P$1") (pintype "bidirectional"))
      (node (ref "U1") (pin "GND") (pinfunction "VSS_GND") (pintype "bidirectional"))
      (node (ref "U10") (pin "AD2") (pinfunction "VBUS_AD2") (pintype "bidirectional"))
      (node (ref "U10") (pin "B7") (pinfunction "VSS_B7") (pintype "bidirectional"))
      (node (ref "U10") (pin "F23") (pinfunction "VSS_PA_F23") (pintype "bidirectional"))
      (node (ref "U10") (pin "GND") (pinfunction "VSS_GND") (pintype "bidirectional"))
      (node (ref "U11") (pin "2") (pinfunction "GND_2") (pintype "bidirectional"))
      (node (ref "U12") (pin "3") (pinfunction "GND_3") (pintype "bidirectional"))
      (node (ref "U2") (pin "1") (pinfunction "GND_1") (pintype "bidirectional"))
      (node (ref "U2") (pin "15") (pinfunction "GND_15") (pintype "bidirectional"))
      (node (ref "U2") (pin "16") (pinfunction "GND_16") (pintype "bidirectional"))
      (node (ref "U2") (pin "17") (pinfunction "GND_17") (pintype "bidirectional"))
      (node (ref "U2") (pin "5") (pinfunction "~{EN}_5") (pintype "bidirectional"))
      (node (ref "U2") (pin "6") (pinfunction "GND_6") (pintype "bidirectional"))
      (node (ref "U2") (pin "PAD") (pinfunction "GND_PAD") (pintype "bidirectional"))
      (node (ref "U3") (pin "GND") (pinfunction "GND_GND") (pintype "bidirectional"))
      (node (ref "U4") (pin "17") (pinfunction "GND_17") (pintype "power_in"))
      (node (ref "U4") (pin "20") (pinfunction "GND_20") (pintype "power_in"))
      (node (ref "U4") (pin "24") (pinfunction "GND_24") (pintype "power_in"))
      (node (ref "U4") (pin "26") (pinfunction "TEST_26") (pintype "input"))
      (node (ref "U4") (pin "4") (pinfunction "GND_4") (pintype "power_in"))
      (node (ref "U6") (pin "5") (pinfunction "GND_5") (pintype "bidirectional"))
      (node (ref "U6") (pin "6") (pinfunction "GND_6") (pintype "bidirectional"))
      (node (ref "U6") (pin "7") (pinfunction "GND_7") (pintype "bidirectional"))
      (node (ref "U6") (pin "8") (pinfunction "GND_8") (pintype "bidirectional"))
      (node (ref "U7") (pin "3") (pinfunction "GND_3") (pintype "bidirectional"))
      (node (ref "U8") (pin "2") (pinfunction "GND_2") (pintype "bidirectional"))
      (node (ref "U8") (pin "3") (pinfunction "A0_3") (pintype "bidirectional"))
      (node (ref "U8") (pin "EP") (pinfunction "GND_EP") (pintype "bidirectional"))
      (node (ref "U9") (pin "4") (pinfunction "GND_4") (pintype "bidirectional"))
      (node (ref "X1") (pin "2") (pinfunction "GND_2") (pintype "bidirectional"))
      (node (ref "X1") (pin "4") (pinfunction "GND_4") (pintype "bidirectional"))
    )
    (net (code "7") (name "LBST") (class "Default")
      (node (ref "L5") (pin "P$1") (pinfunction "1_P$1") (pintype "bidirectional"))
      (node (ref "U10") (pin "AC15") (pinfunction "P0.19_AC15") (pintype "bidirectional"))
      (node (ref "U2") (pin "20") (pinfunction "LBST_20") (pintype "bidirectional"))
    )
    (net (code "8") (name "LED_BLUE") (class "Default")
      (node (ref "R3") (pin "2") (pinfunction "2_2") (pintype "passive"))
      (node (ref "U10") (pin "K2") (pinfunction "P0.05/AIN3_K2") (pintype "bidirectional"))
    )
    (net (code "9") (name "LED_GREEN") (class "Default")
      (node (ref "R2") (pin "2") (pinfunction "2_2") (pintype "passive"))
      (node (ref "U10") (pin "L1") (pinfunction "P0.06_L1") (pintype "bidirectional"))
    )
    (net (code "10") (name "LED_RED") (class "Default")
      (node (ref "R1") (pin "2") (pinfunction "2_2") (pintype "passive"))
      (node (ref "U10") (pin "J1") (pinfunction "P0.04/AIN2_J1") (pintype "bidirectional"))
    )
    (net (code "11") (name "MISO") (class "Default")
      (node (ref "TP4") (pin "P$1") (pinfunction "TESTPOINT_P$1") (pintype "bidirectional"))
      (node (ref "U1") (pin "6") (pinfunction "SDO_6") (pintype "bidirectional"))
      (node (ref "U10") (pin "R1") (pinfunction "P1.09_R1") (pintype "bidirectional"))
      (node (ref "U6") (pin "3") (pinfunction "MISO/SA0_3") (pintype "bidirectional"))
    )
    (net (code "12") (name "MOSI") (class "Default")
      (node (ref "TP5") (pin "P$1") (pinfunction "TESTPOINT_P$1") (pintype "bidirectional"))
      (node (ref "U1") (pin "9") (pinfunction "SDI_9") (pintype "bidirectional"))
      (node (ref "U10") (pin "N1") (pinfunction "P0.08_N1") (pintype "bidirectional"))
      (node (ref "U6") (pin "4") (pinfunction "MOSI/SDA_4") (pintype "bidirectional"))
    )
    (net (code "13") (name "Net-(A2-ANTENNA)") (class "Default")
      (node (ref "A2") (pin "S1") (pinfunction "ANTENNA_S1") (pintype "bidirectional"))
      (node (ref "C2") (pin "1") (pinfunction "1_1") (pintype "bidirectional"))
      (node (ref "L1") (pin "1") (pinfunction "1_1") (pintype "bidirectional"))
    )
    (net (code "14") (name "Net-(D2-B)") (class "Default")
      (node (ref "D2") (pin "3") (pinfunction "B_3") (pintype "output"))
      (node (ref "R3") (pin "1") (pinfunction "1_1") (pintype "passive"))
    )
    (net (code "15") (name "Net-(D2-G)") (class "Default")
      (node (ref "D2") (pin "4") (pinfunction "G_4") (pintype "output"))
      (node (ref "R2") (pin "1") (pinfunction "1_1") (pintype "passive"))
    )
    (net (code "16") (name "Net-(D2-R)") (class "Default")
      (node (ref "D2") (pin "2") (pinfunction "R_2") (pintype "output"))
      (node (ref "R1") (pin "1") (pinfunction "1_1") (pintype "passive"))
    )
    (net (code "17") (name "Net-(J5-D+)") (class "Default")
      (node (ref "J5") (pin "3") (pinfunction "D+_3") (pintype "bidirectional"))
      (node (ref "U4") (pin "14") (pinfunction "USBDP_14") (pintype "bidirectional"))
    )
    (net (code "18") (name "Net-(J5-D-)") (class "Default")
      (node (ref "J5") (pin "2") (pinfunction "D-_2") (pintype "bidirectional"))
      (node (ref "U4") (pin "15") (pinfunction "USBDM_15") (pintype "bidirectional"))
    )
    (net (code "19") (name "Net-(L2-Pad2)") (class "Default")
      (node (ref "L2") (pin "2") (pinfunction "2_2") (pintype "bidirectional"))
      (node (ref "L4") (pin "1") (pinfunction "1_1") (pintype "bidirectional"))
    )
    (net (code "20") (name "Net-(Q1A-D)") (class "Default")
      (node (ref "Q1") (pin "6") (pinfunction "D_6") (pintype "passive"))
      (node (ref "U9") (pin "3") (pinfunction "SCL_3") (pintype "bidirectional"))
    )
    (net (code "21") (name "Net-(Q1B-D)") (class "Default")
      (node (ref "Q1") (pin "3") (pinfunction "D_3") (pintype "passive"))
      (node (ref "U9") (pin "2") (pinfunction "SDA_2") (pintype "bidirectional"))
    )
    (net (code "22") (name "Net-(Q2A-D)") (class "Default")
      (node (ref "Q2") (pin "6") (pinfunction "D_6") (pintype "passive"))
      (node (ref "U11") (pin "6") (pinfunction "SCL_6") (pintype "bidirectional"))
    )
    (net (code "23") (name "Net-(Q2B-D)") (class "Default")
      (node (ref "Q2") (pin "3") (pinfunction "D_3") (pintype "passive"))
      (node (ref "U11") (pin "1") (pinfunction "SDA_1") (pintype "bidirectional"))
    )
    (net (code "24") (name "Net-(Q3A-D)") (class "Default")
      (node (ref "Q3") (pin "6") (pinfunction "D_6") (pintype "passive"))
      (node (ref "U8") (pin "5") (pinfunction "SCL_5") (pintype "bidirectional"))
    )
    (net (code "25") (name "Net-(Q3B-D)") (class "Default")
      (node (ref "Q3") (pin "3") (pinfunction "D_3") (pintype "passive"))
      (node (ref "U8") (pin "6") (pinfunction "SDA_6") (pintype "bidirectional"))
    )
    (net (code "26") (name "Net-(Q4A-D)") (class "Default")
      (node (ref "Q4") (pin "6") (pinfunction "D_6") (pintype "passive"))
      (node (ref "U12") (pin "2") (pinfunction "SCL_2") (pintype "bidirectional"))
    )
    (net (code "27") (name "Net-(Q4B-D)") (class "Default")
      (node (ref "Q4") (pin "3") (pinfunction "D_3") (pintype "passive"))
      (node (ref "U12") (pin "6") (pinfunction "SDA_6") (pintype "bidirectional"))
    )
    (net (code "28") (name "Net-(Q5A-D)") (class "Default")
      (node (ref "C11") (pin "1") (pinfunction "1_1") (pintype "bidirectional"))
      (node (ref "C28") (pin "1") (pinfunction "1_1") (pintype "bidirectional"))
      (node (ref "Q5") (pin "6") (pinfunction "D_6") (pintype "passive"))
      (node (ref "U2") (pin "19") (pinfunction "VSTOR_19") (pintype "bidirectional"))
      (node (ref "U2") (pin "3") (pinfunction "VOC_SAMP_3") (pintype "bidirectional"))
    )
    (net (code "29") (name "Net-(Q5A-G)") (class "Default")
      (node (ref "Q5") (pin "2") (pinfunction "G_2") (pintype "passive"))
      (node (ref "Q5") (pin "5") (pinfunction "G_5") (pintype "passive"))
      (node (ref "U2") (pin "9") (pinfunction "~{VBAT_SEC_ON}_9") (pintype "bidirectional"))
    )
    (net (code "30") (name "Net-(Q5A-S)") (class "Default")
      (node (ref "Q5") (pin "1") (pinfunction "S_1") (pintype "passive"))
      (node (ref "Q5") (pin "4") (pinfunction "S_4") (pintype "passive"))
    )
    (net (code "31") (name "Net-(Q6A-G)") (class "Default")
      (node (ref "Q6") (pin "2") (pinfunction "G_2") (pintype "passive"))
      (node (ref "Q6") (pin "5") (pinfunction "G_5") (pintype "passive"))
      (node (ref "U2") (pin "10") (pinfunction "~{VBAT_PRI_ON}_10") (pintype "bidirectional"))
    )
    (net (code "32") (name "Net-(Q6A-S)") (class "Default")
      (node (ref "Q6") (pin "1") (pinfunction "S_1") (pintype "passive"))
      (node (ref "Q6") (pin "4") (pinfunction "S_4") (pintype "passive"))
    )
    (net (code "33") (name "Net-(Q7A-D)") (class "Default")
      (node (ref "Q7") (pin "6") (pinfunction "D_6") (pintype "passive"))
      (node (ref "U12") (pin "1") (pinfunction "VDD_1") (pintype "bidirectional"))
    )
    (net (code "34") (name "Net-(Q7B-D)") (class "Default")
      (node (ref "Q7") (pin "3") (pinfunction "D_3") (pintype "passive"))
      (node (ref "U8") (pin "1") (pinfunction "VCC_1") (pintype "bidirectional"))
    )
    (net (code "35") (name "Net-(Q8A-D)") (class "Default")
      (node (ref "Q8") (pin "6") (pinfunction "D_6") (pintype "passive"))
      (node (ref "U9") (pin "1") (pinfunction "VDD_1") (pintype "bidirectional"))
    )
    (net (code "36") (name "Net-(Q8B-D)") (class "Default")
      (node (ref "Q8") (pin "3") (pinfunction "D_3") (pintype "passive"))
      (node (ref "U11") (pin "5") (pinfunction "VCC_5") (pintype "bidirectional"))
    )
    (net (code "37") (name "Net-(Q10A-D)") (class "Default")
      (node (ref "Q10") (pin "6") (pinfunction "D_6") (pintype "passive"))
      (node (ref "U3") (pin "VCC") (pinfunction "VCC_VCC") (pintype "bidirectional"))
    )
    (net (code "38") (name "Net-(S1-P$2)") (class "Default")
      (node (ref "R10") (pin "1") (pinfunction "1_1") (pintype "passive"))
      (node (ref "S1") (pin "2") (pinfunction "P$2_2") (pintype "passive"))
      (node (ref "U1") (pin "3") (pinfunction "~{EXTR}_3") (pintype "bidirectional"))
    )
    (net (code "39") (name "Net-(U1-AF)") (class "Default")
      (node (ref "C7") (pin "1") (pinfunction "1_1") (pintype "bidirectional"))
      (node (ref "U1") (pin "14") (pinfunction "AF_14") (pintype "bidirectional"))
    )
    (net (code "40") (name "Net-(U1-XI)") (class "Default")
      (node (ref "C33") (pin "1") (pinfunction "1_1") (pintype "bidirectional"))
      (node (ref "U1") (pin "16") (pinfunction "XI_16") (pintype "bidirectional"))
      (node (ref "X4") (pin "1") (pinfunction "1_1") (pintype "bidirectional"))
    )
    (net (code "41") (name "Net-(U1-XO)") (class "Default")
      (node (ref "C34") (pin "1") (pinfunction "1_1") (pintype "bidirectional"))
      (node (ref "U1") (pin "15") (pinfunction "XO_15") (pintype "bidirectional"))
      (node (ref "X4") (pin "2") (pinfunction "2_2") (pintype "bidirectional"))
    )
    (net (code "42") (name "Net-(U2-OK_HYST)") (class "Default")
      (node (ref "R17") (pin "2") (pinfunction "2_2") (pintype "passive"))
      (node (ref "R4") (pin "1") (pinfunction "1_1") (pintype "passive"))
      (node (ref "U2") (pin "11") (pinfunction "OK_HYST_11") (pintype "bidirectional"))
    )
    (net (code "43") (name "Net-(U2-OK_PROG)") (class "Default")
      (node (ref "R17") (pin "1") (pinfunction "1_1") (pintype "passive"))
      (node (ref "R18") (pin "2") (pinfunction "2_2") (pintype "passive"))
      (node (ref "U2") (pin "12") (pinfunction "OK_PROG_12") (pintype "bidirectional"))
    )
    (net (code "44") (name "Net-(U2-VBAT_OV)") (class "Default")
      (node (ref "R14") (pin "1") (pinfunction "1_1") (pintype "passive"))
      (node (ref "R21") (pin "2") (pinfunction "2_2") (pintype "passive"))
      (node (ref "U2") (pin "7") (pinfunction "VBAT_OV_7") (pintype "bidirectional"))
    )
    (net (code "45") (name "Net-(U2-VRDIV)") (class "Default")
      (node (ref "R14") (pin "2") (pinfunction "2_2") (pintype "passive"))
      (node (ref "R4") (pin "2") (pinfunction "2_2") (pintype "passive"))
      (node (ref "U2") (pin "8") (pinfunction "VRDIV_8") (pintype "bidirectional"))
    )
    (net (code "46") (name "Net-(U2-VREF_SAMP)") (class "Default")
      (node (ref "C10") (pin "1") (pinfunction "1_1") (pintype "bidirectional"))
      (node (ref "U2") (pin "4") (pinfunction "VREF_SAMP_4") (pintype "bidirectional"))
    )
    (net (code "47") (name "Net-(U4-3V3OUT)") (class "Default")
      (node (ref "C21") (pin "1") (pinfunction "1_1") (pintype "bidirectional"))
      (node (ref "U4") (pin "16") (pinfunction "3V3OUT_16") (pintype "output"))
    )
    (net (code "48") (name "Net-(U4-RXD)") (class "Default")
      (node (ref "SJ4") (pin "1") (pinfunction "1_1") (pintype "passive"))
      (node (ref "U4") (pin "2") (pinfunction "RXD_2") (pintype "input"))
    )
    (net (code "49") (name "Net-(U4-TXD)") (class "Default")
      (node (ref "SJ5") (pin "1") (pinfunction "1_1") (pintype "passive"))
      (node (ref "U4") (pin "30") (pinfunction "TXD_30") (pintype "output"))
    )
    (net (code "50") (name "Net-(U4-VCCIO)") (class "Default")
      (node (ref "SJ2") (pin "2") (pinfunction "2_2") (pintype "passive"))
      (node (ref "U4") (pin "1") (pinfunction "VCCIO_1") (pintype "power_in"))
    )
    (net (code "51") (name "Net-(U4-~{RESET})") (class "Default")
      (node (ref "SJ3") (pin "2") (pinfunction "2_2") (pintype "passive"))
      (node (ref "U4") (pin "18") (pinfunction "~{RESET}_18") (pintype "input"))
    )
    (net (code "52") (name "Net-(U7-EN)") (class "Default")
      (node (ref "R22") (pin "1") (pinfunction "1_1") (pintype "passive"))
      (node (ref "U7") (pin "6") (pinfunction "EN_6") (pintype "bidirectional"))
    )
    (net (code "53") (name "Net-(U7-SEL)") (class "Default")
      (node (ref "R13") (pin "2") (pinfunction "2_2") (pintype "passive"))
      (node (ref "U7") (pin "4") (pinfunction "SEL_4") (pintype "bidirectional"))
    )
    (net (code "54") (name "Net-(U10-ANT)") (class "Default")
      (node (ref "C1") (pin "1") (pinfunction "1_1") (pintype "bidirectional"))
      (node (ref "L1") (pin "2") (pinfunction "2_2") (pintype "bidirectional"))
      (node (ref "U10") (pin "H23") (pinfunction "ANT_H23") (pintype "bidirectional"))
    )
    (net (code "55") (name "Net-(U10-DCC)") (class "Default")
      (node (ref "L4") (pin "2") (pinfunction "2_2") (pintype "bidirectional"))
      (node (ref "U10") (pin "B3") (pinfunction "DCC_B3") (pintype "bidirectional"))
    )
    (net (code "56") (name "Net-(U10-DEC1)") (class "Default")
      (node (ref "C15") (pin "1") (pinfunction "1_1") (pintype "bidirectional"))
      (node (ref "U10") (pin "C1") (pinfunction "DEC1_C1") (pintype "bidirectional"))
    )
    (net (code "57") (name "Net-(U10-DEC3)") (class "Default")
      (node (ref "C8") (pin "1") (pinfunction "1_1") (pintype "bidirectional"))
      (node (ref "U10") (pin "D23") (pinfunction "DEC3_D23") (pintype "bidirectional"))
    )
    (net (code "58") (name "Net-(U10-DEC4)") (class "Default")
      (node (ref "C12") (pin "1") (pinfunction "1_1") (pintype "bidirectional"))
      (node (ref "C23") (pin "1") (pinfunction "1_1") (pintype "bidirectional"))
      (node (ref "L2") (pin "1") (pinfunction "1_1") (pintype "bidirectional"))
      (node (ref "U10") (pin "B5") (pinfunction "DEC4_B5") (pintype "bidirectional"))
      (node (ref "U10") (pin "E24") (pinfunction "DEC6_E24") (pintype "bidirectional"))
    )
    (net (code "59") (name "Net-(U10-DEC5)") (class "Default")
      (node (ref "C9") (pin "1") (pinfunction "1_1") (pintype "bidirectional"))
      (node (ref "U10") (pin "N24") (pinfunction "DEC5_N24") (pintype "bidirectional"))
    )
    (net (code "60") (name "Net-(U10-P0.00{slash}XL1)") (class "Default")
      (node (ref "C6") (pin "2") (pinfunction "2_2") (pintype "bidirectional"))
      (node (ref "U10") (pin "D2") (pinfunction "P0.00/XL1_D2") (pintype "bidirectional"))
      (node (ref "X3") (pin "A") (pinfunction "1_A") (pintype "bidirectional"))
    )
    (net (code "61") (name "Net-(U10-P0.01{slash}XL2)") (class "Default")
      (node (ref "C5") (pin "2") (pinfunction "2_2") (pintype "bidirectional"))
      (node (ref "U10") (pin "F2") (pinfunction "P0.01/XL2_F2") (pintype "bidirectional"))
      (node (ref "X3") (pin "B") (pinfunction "2_B") (pintype "bidirectional"))
    )
    (net (code "62") (name "Net-(U10-XC1)") (class "Default")
      (node (ref "C3") (pin "2") (pinfunction "2_2") (pintype "bidirectional"))
      (node (ref "U10") (pin "B24") (pinfunction "XC1_B24") (pintype "bidirectional"))
      (node (ref "X1") (pin "3") (pinfunction "2_3") (pintype "bidirectional"))
    )
    (net (code "63") (name "Net-(U10-XC2)") (class "Default")
      (node (ref "C4") (pin "2") (pinfunction "2_2") (pintype "bidirectional"))
      (node (ref "U10") (pin "A23") (pinfunction "XC2_A23") (pintype "bidirectional"))
      (node (ref "X1") (pin "1") (pinfunction "1_1") (pintype "bidirectional"))
    )
    (net (code "64") (name "PIR_OUT") (class "Default")
      (node (ref "TP22") (pin "P$1") (pinfunction "TESTPOINT_P$1") (pintype "bidirectional"))
      (node (ref "U10") (pin "AC11") (pinfunction "P0.16_AC11") (pintype "bidirectional"))
      (node (ref "U3") (pin "OUT") (pinfunction "OUT_OUT") (pintype "bidirectional"))
    )
    (net (code "65") (name "RTC_CS") (class "Default")
      (node (ref "TP6") (pin "P$1") (pinfunction "TESTPOINT_P$1") (pintype "bidirectional"))
      (node (ref "U1") (pin "12") (pinfunction "~{CS}_12") (pintype "bidirectional"))
      (node (ref "U10") (pin "B17") (pinfunction "P1.12_B17") (pintype "bidirectional"))
    )
    (net (code "66") (name "SCK") (class "Default")
      (node (ref "TP3") (pin "P$1") (pinfunction "TESTPOINT_P$1") (pintype "bidirectional"))
      (node (ref "U1") (pin "7") (pinfunction "SCL_7") (pintype "bidirectional"))
      (node (ref "U10") (pin "U1") (pinfunction "P0.12_U1") (pintype "bidirectional"))
      (node (ref "U6") (pin "1") (pinfunction "SCL/SPC_1") (pintype "bidirectional"))
    )
    (net (code "67") (name "SCL") (class "Default")
      (node (ref "Q1") (pin "1") (pinfunction "S_1") (pintype "passive"))
      (node (ref "Q2") (pin "1") (pinfunction "S_1") (pintype "passive"))
      (node (ref "Q3") (pin "1") (pinfunction "S_1") (pintype "passive"))
      (node (ref "Q4") (pin "1") (pinfunction "S_1") (pintype "passive"))
      (node (ref "R6") (pin "1") (pinfunction "1_1") (pintype "passive"))
      (node (ref "TP2") (pin "P$1") (pinfunction "TESTPOINT_P$1") (pintype "bidirectional"))
      (node (ref "U10") (pin "AC9") (pinfunction "P0.14_AC9") (pintype "bidirectional"))
    )
    (net (code "68") (name "SDA") (class "Default")
      (node (ref "Q1") (pin "4") (pinfunction "S_4") (pintype "passive"))
      (node (ref "Q2") (pin "4") (pinfunction "S_4") (pintype "passive"))
      (node (ref "Q3") (pin "4") (pinfunction "S_4") (pintype "passive"))
      (node (ref "Q4") (pin "4") (pinfunction "S_4") (pintype "passive"))
      (node (ref "R7") (pin "1") (pinfunction "1_1") (pintype "passive"))
      (node (ref "TP1") (pin "P$1") (pinfunction "TESTPOINT_P$1") (pintype "bidirectional"))
      (node (ref "U10") (pin "AD10") (pinfunction "P0.15_AD10") (pintype "bidirectional"))
    )
    (net (code "69") (name "SW") (class "Default")
      (node (ref "L3") (pin "P$2") (pinfunction "2_P$2") (pintype "bidirectional"))
      (node (ref "TP25") (pin "P$1") (pinfunction "TESTPOINT_P$1") (pintype "bidirectional"))
      (node (ref "U10") (pin "AD8") (pinfunction "P0.13_AD8") (pintype "bidirectional"))
      (node (ref "U7") (pin "2") (pinfunction "LX_2") (pintype "bidirectional"))
    )
    (net (code "70") (name "SWDCLK") (class "Default")
      (node (ref "J1") (pin "4") (pinfunction "SWDCLK_4") (pintype "bidirectional"))
      (node (ref "U10") (pin "AA24") (pinfunction "SWDCLK_AA24") (pintype "bidirectional"))
    )
    (net (code "71") (name "SWDIO") (class "Default")
      (node (ref "J1") (pin "2") (pinfunction "SWDIO_2") (pintype "bidirectional"))
      (node (ref "U10") (pin "AC24") (pinfunction "SWDIO_AC24") (pintype "bidirectional"))
    )
    (net (code "72") (name "USB_5V") (class "Default")
      (node (ref "J5") (pin "1") (pinfunction "+5V_1") (pintype "bidirectional"))
      (node (ref "U4") (pin "19") (pinfunction "VCC_19") (pintype "power_in"))
    )
    (net (code "73") (name "VBAT") (class "Default")
      (node (ref "BT2") (pin "POS1") (pinfunction "+_POS1") (pintype "bidirectional"))
      (node (ref "BT2") (pin "POS2") (pinfunction "+_POS2") (pintype "bidirectional"))
      (node (ref "BT2") (pin "POS3") (pinfunction "+_POS3") (pintype "bidirectional"))
      (node (ref "BT2") (pin "POS4") (pinfunction "+_POS4") (pintype "bidirectional"))
      (node (ref "BT3") (pin "POS1") (pinfunction "+_POS1") (pintype "bidirectional"))
      (node (ref "BT3") (pin "POS2") (pinfunction "+_POS2") (pintype "bidirectional"))
      (node (ref "BT3") (pin "POS3") (pinfunction "+_POS3") (pintype "bidirectional"))
      (node (ref "BT3") (pin "POS4") (pinfunction "+_POS4") (pintype "bidirectional"))
      (node (ref "BT4") (pin "+") (pinfunction "+_+") (pintype "bidirectional"))
      (node (ref "Q6") (pin "6") (pinfunction "D_6") (pintype "passive"))
      (node (ref "U1") (pin "5") (pinfunction "VBAT_5") (pintype "bidirectional"))
      (node (ref "U10") (pin "A10") (pinfunction "P0.29/AIN5_A10") (pintype "bidirectional"))
      (node (ref "U2") (pin "14") (pinfunction "VBAT_PRI_14") (pintype "bidirectional"))
    )
    (net (code "74") (name "VBAT_OK") (class "Default")
      (node (ref "U10") (pin "R24") (pinfunction "P1.06_R24") (pintype "bidirectional"))
      (node (ref "U2") (pin "13") (pinfunction "VBAT_OK_13") (pintype "bidirectional"))
    )
    (net (code "75") (name "VCC") (class "Default")
      (node (ref "C13") (pin "1") (pinfunction "1_1") (pintype "bidirectional"))
      (node (ref "C14") (pin "1") (pinfunction "1_1") (pintype "bidirectional"))
      (node (ref "C16") (pin "1") (pinfunction "1_1") (pintype "bidirectional"))
      (node (ref "C17") (pin "1") (pinfunction "1_1") (pintype "bidirectional"))
      (node (ref "C18") (pin "1") (pinfunction "1_1") (pintype "bidirectional"))
      (node (ref "C19") (pin "1") (pinfunction "1_1") (pintype "bidirectional"))
      (node (ref "C20") (pin "1") (pinfunction "1_1") (pintype "bidirectional"))
      (node (ref "C22") (pin "1") (pinfunction "1_1") (pintype "bidirectional"))
      (node (ref "C24") (pin "1") (pinfunction "1_1") (pintype "bidirectional"))
      (node (ref "C25") (pin "1") (pinfunction "1_1") (pintype "bidirectional"))
      (node (ref "C26") (pin "1") (pinfunction "1_1") (pintype "bidirectional"))
      (node (ref "C27") (pin "1") (pinfunction "1_1") (pintype "bidirectional"))
      (node (ref "C31") (pin "1") (pinfunction "1_1") (pintype "bidirectional"))
      (node (ref "C32") (pin "1") (pinfunction "1_1") (pintype "bidirectional"))
      (node (ref "D2") (pin "1") (pinfunction "VDD_1") (pintype "bidirectional"))
      (node (ref "J1") (pin "1") (pinfunction "VCC_1") (pintype "bidirectional"))
      (node (ref "Q10") (pin "1") (pinfunction "S_1") (pintype "passive"))
      (node (ref "Q7") (pin "1") (pinfunction "S_1") (pintype "passive"))
      (node (ref "Q7") (pin "4") (pinfunction "S_4") (pintype "passive"))
      (node (ref "Q8") (pin "1") (pinfunction "S_1") (pintype "passive"))
      (node (ref "Q8") (pin "4") (pinfunction "S_4") (pintype "passive"))
      (node (ref "R10") (pin "2") (pinfunction "2_2") (pintype "passive"))
      (node (ref "R11") (pin "2") (pinfunction "2_2") (pintype "passive"))
      (node (ref "R12") (pin "2") (pinfunction "2_2") (pintype "passive"))
      (node (ref "R23") (pin "2") (pinfunction "2_2") (pintype "passive"))
      (node (ref "R24") (pin "2") (pinfunction "2_2") (pintype "passive"))
      (node (ref "R25") (pin "2") (pinfunction "2_2") (pintype "passive"))
      (node (ref "R26") (pin "2") (pinfunction "2_2") (pintype "passive"))
      (node (ref "R27") (pin "2") (pinfunction "2_2") (pintype "passive"))
      (node (ref "R6") (pin "2") (pinfunction "2_2") (pintype "passive"))
      (node (ref "R7") (pin "2") (pinfunction "2_2") (pintype "passive"))
      (node (ref "R8") (pin "2") (pinfunction "2_2") (pintype "passive"))
      (node (ref "R9") (pin "2") (pinfunction "2_2") (pintype "passive"))
      (node (ref "SJ2") (pin "1") (pinfunction "1_1") (pintype "passive"))
      (node (ref "TP26") (pin "P$1") (pinfunction "TESTPOINT_P$1") (pintype "bidirectional"))
      (node (ref "U1") (pin "13") (pinfunction "VCC_13") (pintype "bidirectional"))
      (node (ref "U10") (pin "A22") (pinfunction "VDD_A22") (pintype "bidirectional"))
      (node (ref "U10") (pin "AD14") (pinfunction "VDD_AD14") (pintype "bidirectional"))
      (node (ref "U10") (pin "AD23") (pinfunction "VDD_AD23") (pintype "bidirectional"))
      (node (ref "U10") (pin "B1") (pinfunction "VDD_B1") (pintype "bidirectional"))
      (node (ref "U10") (pin "W1") (pinfunction "VDD_W1") (pintype "bidirectional"))
      (node (ref "U10") (pin "Y2") (pinfunction "VDDH_Y2") (pintype "bidirectional"))
      (node (ref "U6") (pin "10") (pinfunction "VDD_IO_10") (pintype "bidirectional"))
      (node (ref "U6") (pin "9") (pinfunction "VCC_9") (pintype "bidirectional"))
      (node (ref "U7") (pin "1") (pinfunction "OUT_1") (pintype "bidirectional"))
    )
    (net (code "76") (name "VSEC") (class "Default")
      (node (ref "BT1") (pin "+") (pinfunction "+_+") (pintype "bidirectional"))
      (node (ref "TP24") (pin "P$1") (pinfunction "TESTPOINT_P$1") (pintype "bidirectional"))
      (node (ref "U10") (pin "A8") (pinfunction "P0.31/AIN7_A8") (pintype "bidirectional"))
      (node (ref "U2") (pin "18") (pinfunction "VBAT_SEC_18") (pintype "bidirectional"))
    )
    (net (code "77") (name "VSOL") (class "Default")
      (node (ref "C29") (pin "1") (pinfunction "1_1") (pintype "bidirectional"))
      (node (ref "D1") (pin "+") (pinfunction "V+_+") (pintype "bidirectional"))
      (node (ref "L5") (pin "P$2") (pinfunction "2_P$2") (pintype "bidirectional"))
      (node (ref "TP23") (pin "P$1") (pinfunction "TESTPOINT_P$1") (pintype "bidirectional"))
      (node (ref "U10") (pin "B9") (pinfunction "P0.30/AIN6_B9") (pintype "bidirectional"))
      (node (ref "U2") (pin "2") (pinfunction "VIN_DC_2") (pintype "bidirectional"))
    )
    (net (code "78") (name "VSW") (class "Default")
      (node (ref "C30") (pin "1") (pinfunction "1_1") (pintype "bidirectional"))
      (node (ref "L3") (pin "P$1") (pinfunction "1_P$1") (pintype "bidirectional"))
      (node (ref "Q5") (pin "3") (pinfunction "D_3") (pintype "passive"))
      (node (ref "Q6") (pin "3") (pinfunction "D_3") (pintype "passive"))
      (node (ref "R22") (pin "2") (pinfunction "2_2") (pintype "passive"))
      (node (ref "U7") (pin "5") (pinfunction "IN_5") (pintype "bidirectional"))
    )
    (net (code "79") (name "WDI") (class "Default")
      (node (ref "R12") (pin "1") (pinfunction "1_1") (pintype "passive"))
      (node (ref "TP16") (pin "P$1") (pinfunction "TESTPOINT_P$1") (pintype "bidirectional"))
      (node (ref "U1") (pin "2") (pinfunction "WDI_2") (pintype "bidirectional"))
      (node (ref "U10") (pin "A12") (pinfunction "P0.02/AIN0_A12") (pintype "bidirectional"))
    )
    (net (code "80") (name "unconnected-(J1-SWO-Pad6)") (class "Default")
      (node (ref "J1") (pin "6") (pinfunction "SWO_6") (pintype "bidirectional"))
    )
    (net (code "81") (name "unconnected-(J5-ID-Pad4)") (class "Default")
      (node (ref "J5") (pin "4") (pinfunction "ID_4") (pintype "bidirectional"))
    )
    (net (code "82") (name "unconnected-(U1-EXTI-Pad10)") (class "Default")
      (node (ref "U1") (pin "10") (pinfunction "EXTI_10") (pintype "bidirectional"))
    )
    (net (code "83") (name "unconnected-(U4-CBUS0-Pad22)") (class "Default")
      (node (ref "U4") (pin "22") (pinfunction "CBUS0_22") (pintype "bidirectional"))
    )
    (net (code "84") (name "unconnected-(U4-CBUS1-Pad21)") (class "Default")
      (node (ref "U4") (pin "21") (pinfunction "CBUS1_21") (pintype "bidirectional"))
    )
    (net (code "85") (name "unconnected-(U4-CBUS2-Pad10)") (class "Default")
      (node (ref "U4") (pin "10") (pinfunction "CBUS2_10") (pintype "bidirectional"))
    )
    (net (code "86") (name "unconnected-(U4-CBUS3-Pad11)") (class "Default")
      (node (ref "U4") (pin "11") (pinfunction "CBUS3_11") (pintype "bidirectional"))
    )
    (net (code "87") (name "unconnected-(U4-CBUS4-Pad9)") (class "Default")
      (node (ref "U4") (pin "9") (pinfunction "CBUS4_9") (pintype "bidirectional"))
    )
    (net (code "88") (name "unconnected-(U4-OSCI-Pad27)") (class "Default")
      (node (ref "U4") (pin "27") (pinfunction "OSCI_27") (pintype "input"))
    )
    (net (code "89") (name "unconnected-(U4-OSCO-Pad28)") (class "Default")
      (node (ref "U4") (pin "28") (pinfunction "OSCO_28") (pintype "output"))
    )
    (net (code "90") (name "unconnected-(U4-~{CTS}-Pad8)") (class "Default")
      (node (ref "U4") (pin "8") (pinfunction "~{CTS}_8") (pintype "input"))
    )
    (net (code "91") (name "unconnected-(U4-~{DCD}-Pad7)") (class "Default")
      (node (ref "U4") (pin "7") (pinfunction "~{DCD}_7") (pintype "input"))
    )
    (net (code "92") (name "unconnected-(U4-~{DSR}-Pad6)") (class "Default")
      (node (ref "U4") (pin "6") (pinfunction "~{DSR}_6") (pintype "input"))
    )
    (net (code "93") (name "unconnected-(U4-~{DTR}-Pad31)") (class "Default")
      (node (ref "U4") (pin "31") (pinfunction "~{DTR}_31") (pintype "output"))
    )
    (net (code "94") (name "unconnected-(U4-~{RI}-Pad3)") (class "Default")
      (node (ref "U4") (pin "3") (pinfunction "~{RI}_3") (pintype "input"))
    )
    (net (code "95") (name "unconnected-(U4-~{RTS}-Pad32)") (class "Default")
      (node (ref "U4") (pin "32") (pinfunction "~{RTS}_32") (pintype "output"))
    )
    (net (code "96") (name "unconnected-(U10-D+-PadAD6)") (class "Default")
      (node (ref "U10") (pin "AD6") (pinfunction "D+_AD6") (pintype "bidirectional"))
    )
    (net (code "97") (name "unconnected-(U10-D--PadAD4)") (class "Default")
      (node (ref "U10") (pin "AD4") (pinfunction "D-_AD4") (pintype "bidirectional"))
    )
    (net (code "98") (name "unconnected-(U10-DCCH-PadAB2)") (class "Default")
      (node (ref "U10") (pin "AB2") (pinfunction "DCCH_AB2") (pintype "bidirectional"))
    )
    (net (code "99") (name "unconnected-(U10-DEC2-PadA18)") (class "Default")
      (node (ref "U10") (pin "A18") (pinfunction "DEC2_A18") (pintype "bidirectional"))
    )
    (net (code "100") (name "unconnected-(U10-DECUSB-PadAC5)") (class "Default")
      (node (ref "U10") (pin "AC5") (pinfunction "DECUSB_AC5") (pintype "bidirectional"))
    )
    (net (code "101") (name "unconnected-(U10-P0.03{slash}AIN1-PadB13)") (class "Default")
      (node (ref "U10") (pin "B13") (pinfunction "P0.03/AIN1_B13") (pintype "bidirectional"))
    )
    (net (code "102") (name "unconnected-(U10-P0.07-PadM2)") (class "Default")
      (node (ref "U10") (pin "M2") (pinfunction "P0.07_M2") (pintype "bidirectional"))
    )
    (net (code "103") (name "unconnected-(U10-P0.09{slash}NFC1-PadL24)") (class "Default")
      (node (ref "U10") (pin "L24") (pinfunction "P0.09/NFC1_L24") (pintype "bidirectional"))
    )
    (net (code "104") (name "unconnected-(U10-P0.10{slash}NFC2-PadJ24)") (class "Default")
      (node (ref "U10") (pin "J24") (pinfunction "P0.10/NFC2_J24") (pintype "bidirectional"))
    )
    (net (code "105") (name "unconnected-(U10-P0.11-PadT2)") (class "Default")
      (node (ref "U10") (pin "T2") (pinfunction "P0.11_T2") (pintype "bidirectional"))
    )
    (net (code "106") (name "unconnected-(U10-P0.28{slash}AIN4-PadB11)") (class "Default")
      (node (ref "U10") (pin "B11") (pinfunction "P0.28/AIN4_B11") (pintype "bidirectional"))
    )
    (net (code "107") (name "unconnected-(U10-P1.01-PadY23)") (class "Default")
      (node (ref "U10") (pin "Y23") (pinfunction "P1.01_Y23") (pintype "bidirectional"))
    )
    (net (code "108") (name "unconnected-(U10-P1.02-PadW24)") (class "Default")
      (node (ref "U10") (pin "W24") (pinfunction "P1.02_W24") (pintype "bidirectional"))
    )
    (net (code "109") (name "unconnected-(U10-P1.03-PadV23)") (class "Default")
      (node (ref "U10") (pin "V23") (pinfunction "P1.03_V23") (pintype "bidirectional"))
    )
    (net (code "110") (name "unconnected-(U10-P1.04-PadU24)") (class "Default")
      (node (ref "U10") (pin "U24") (pinfunction "P1.04_U24") (pintype "bidirectional"))
    )
    (net (code "111") (name "unconnected-(U10-P1.05-PadT23)") (class "Default")
      (node (ref "U10") (pin "T23") (pinfunction "P1.05_T23") (pintype "bidirectional"))
    )
    (net (code "112") (name "unconnected-(U10-P1.07-PadP23)") (class "Default")
      (node (ref "U10") (pin "P23") (pinfunction "P1.07_P23") (pintype "bidirectional"))
    )
    (net (code "113") (name "unconnected-(U10-P1.08-PadP2)") (class "Default")
      (node (ref "U10") (pin "P2") (pinfunction "P1.08_P2") (pintype "bidirectional"))
    )
    (net (code "114") (name "~{CLR_EN}") (class "Default")
      (node (ref "Q4") (pin "2") (pinfunction "G_2") (pintype "passive"))
      (node (ref "Q4") (pin "5") (pinfunction "G_5") (pintype "passive"))
      (node (ref "Q7") (pin "2") (pinfunction "G_2") (pintype "passive"))
      (node (ref "R23") (pin "1") (pinfunction "1_1") (pintype "passive"))
      (node (ref "TP9") (pin "P$1") (pinfunction "TESTPOINT_P$1") (pintype "bidirectional"))
      (node (ref "U10") (pin "AC21") (pinfunction "P0.25_AC21") (pintype "bidirectional"))
    )
    (net (code "115") (name "~{CLR_INT}") (class "Default")
      (node (ref "R8") (pin "1") (pinfunction "1_1") (pintype "passive"))
      (node (ref "TP20") (pin "P$1") (pinfunction "TESTPOINT_P$1") (pintype "bidirectional"))
      (node (ref "U10") (pin "AC19") (pinfunction "P0.23_AC19") (pintype "bidirectional"))
      (node (ref "U12") (pin "5") (pinfunction "INT_5") (pintype "bidirectional"))
    )
    (net (code "116") (name "~{HUM_EN}") (class "Default")
      (node (ref "Q2") (pin "2") (pinfunction "G_2") (pintype "passive"))
      (node (ref "Q2") (pin "5") (pinfunction "G_5") (pintype "passive"))
      (node (ref "Q8") (pin "5") (pinfunction "G_5") (pintype "passive"))
      (node (ref "R26") (pin "1") (pinfunction "1_1") (pintype "passive"))
      (node (ref "TP12") (pin "P$1") (pinfunction "TESTPOINT_P$1") (pintype "bidirectional"))
      (node (ref "U10") (pin "A20") (pinfunction "P1.10_A20") (pintype "bidirectional"))
    )
    (net (code "117") (name "~{LT_EN}") (class "Default")
      (node (ref "Q3") (pin "2") (pinfunction "G_2") (pintype "passive"))
      (node (ref "Q3") (pin "5") (pinfunction "G_5") (pintype "passive"))
      (node (ref "Q7") (pin "5") (pinfunction "G_5") (pintype "passive"))
      (node (ref "R24") (pin "1") (pinfunction "1_1") (pintype "passive"))
      (node (ref "TP10") (pin "P$1") (pinfunction "TESTPOINT_P$1") (pintype "bidirectional"))
      (node (ref "U10") (pin "AD20") (pinfunction "P0.24_AD20") (pintype "bidirectional"))
    )
    (net (code "118") (name "~{LT_INT}") (class "Default")
      (node (ref "R9") (pin "1") (pinfunction "1_1") (pintype "passive"))
      (node (ref "TP21") (pin "P$1") (pinfunction "TESTPOINT_P$1") (pintype "bidirectional"))
      (node (ref "U10") (pin "AD22") (pinfunction "P1.00_AD22") (pintype "bidirectional"))
      (node (ref "U8") (pin "4") (pinfunction "~{INT}_4") (pintype "bidirectional"))
    )
    (net (code "119") (name "~{PIR_EN}") (class "Default")
      (node (ref "Q10") (pin "2") (pinfunction "G_2") (pintype "passive"))
      (node (ref "R27") (pin "1") (pinfunction "1_1") (pintype "passive"))
      (node (ref "TP11") (pin "P$1") (pinfunction "TESTPOINT_P$1") (pintype "bidirectional"))
      (node (ref "U10") (pin "AD12") (pinfunction "P0.17_AD12") (pintype "bidirectional"))
    )
    (net (code "120") (name "~{PR_EN}") (class "Default")
      (node (ref "Q1") (pin "2") (pinfunction "G_2") (pintype "passive"))
      (node (ref "Q1") (pin "5") (pinfunction "G_5") (pintype "passive"))
      (node (ref "Q8") (pin "2") (pinfunction "G_2") (pintype "passive"))
      (node (ref "R25") (pin "1") (pinfunction "1_1") (pintype "passive"))
      (node (ref "TP8") (pin "P$1") (pinfunction "TESTPOINT_P$1") (pintype "bidirectional"))
      (node (ref "U10") (pin "B19") (pinfunction "P1.11_B19") (pintype "bidirectional"))
    )
    (net (code "121") (name "~{RST}") (class "Default")
      (node (ref "J1") (pin "3") (pinfunction "~{RESET}_3") (pintype "bidirectional"))
      (node (ref "R11") (pin "1") (pinfunction "1_1") (pintype "passive"))
      (node (ref "SJ3") (pin "1") (pinfunction "1_1") (pintype "passive"))
      (node (ref "TP17") (pin "P$1") (pinfunction "TESTPOINT_P$1") (pintype "bidirectional"))
      (node (ref "U1") (pin "1") (pinfunction "~{RST}_1") (pintype "bidirectional"))
      (node (ref "U10") (pin "AC13") (pinfunction "P0.18_AC13") (pintype "bidirectional"))
    )
    (net (code "122") (name "~{RTC_IRQ1}") (class "Default")
      (node (ref "TP13") (pin "P$1") (pinfunction "TESTPOINT_P$1") (pintype "bidirectional"))
      (node (ref "U1") (pin "11") (pinfunction "FOUT/~{IRQ1}_11") (pintype "bidirectional"))
      (node (ref "U10") (pin "A16") (pinfunction "P1.13_A16") (pintype "bidirectional"))
    )
    (net (code "123") (name "~{RTC_IRQ2}") (class "Default")
      (node (ref "TP14") (pin "P$1") (pinfunction "TESTPOINT_P$1") (pintype "bidirectional"))
      (node (ref "U1") (pin "4") (pinfunction "~{IRQ2}_4") (pintype "bidirectional"))
      (node (ref "U10") (pin "B15") (pinfunction "P1.14_B15") (pintype "bidirectional"))
    )
    (net (code "124") (name "~{RTC_IRQ3}") (class "Default")
      (node (ref "TP15") (pin "P$1") (pinfunction "TESTPOINT_P$1") (pintype "bidirectional"))
      (node (ref "U1") (pin "8") (pinfunction "CLKOUT/~{IRQ3}_8") (pintype "bidirectional"))
      (node (ref "U10") (pin "A14") (pinfunction "P1.15_A14") (pintype "bidirectional"))
    )
  )
)
